# soap-disp-smd-32-channel-min.net
KiCad netlist of a schematic drawn in EasyEDA
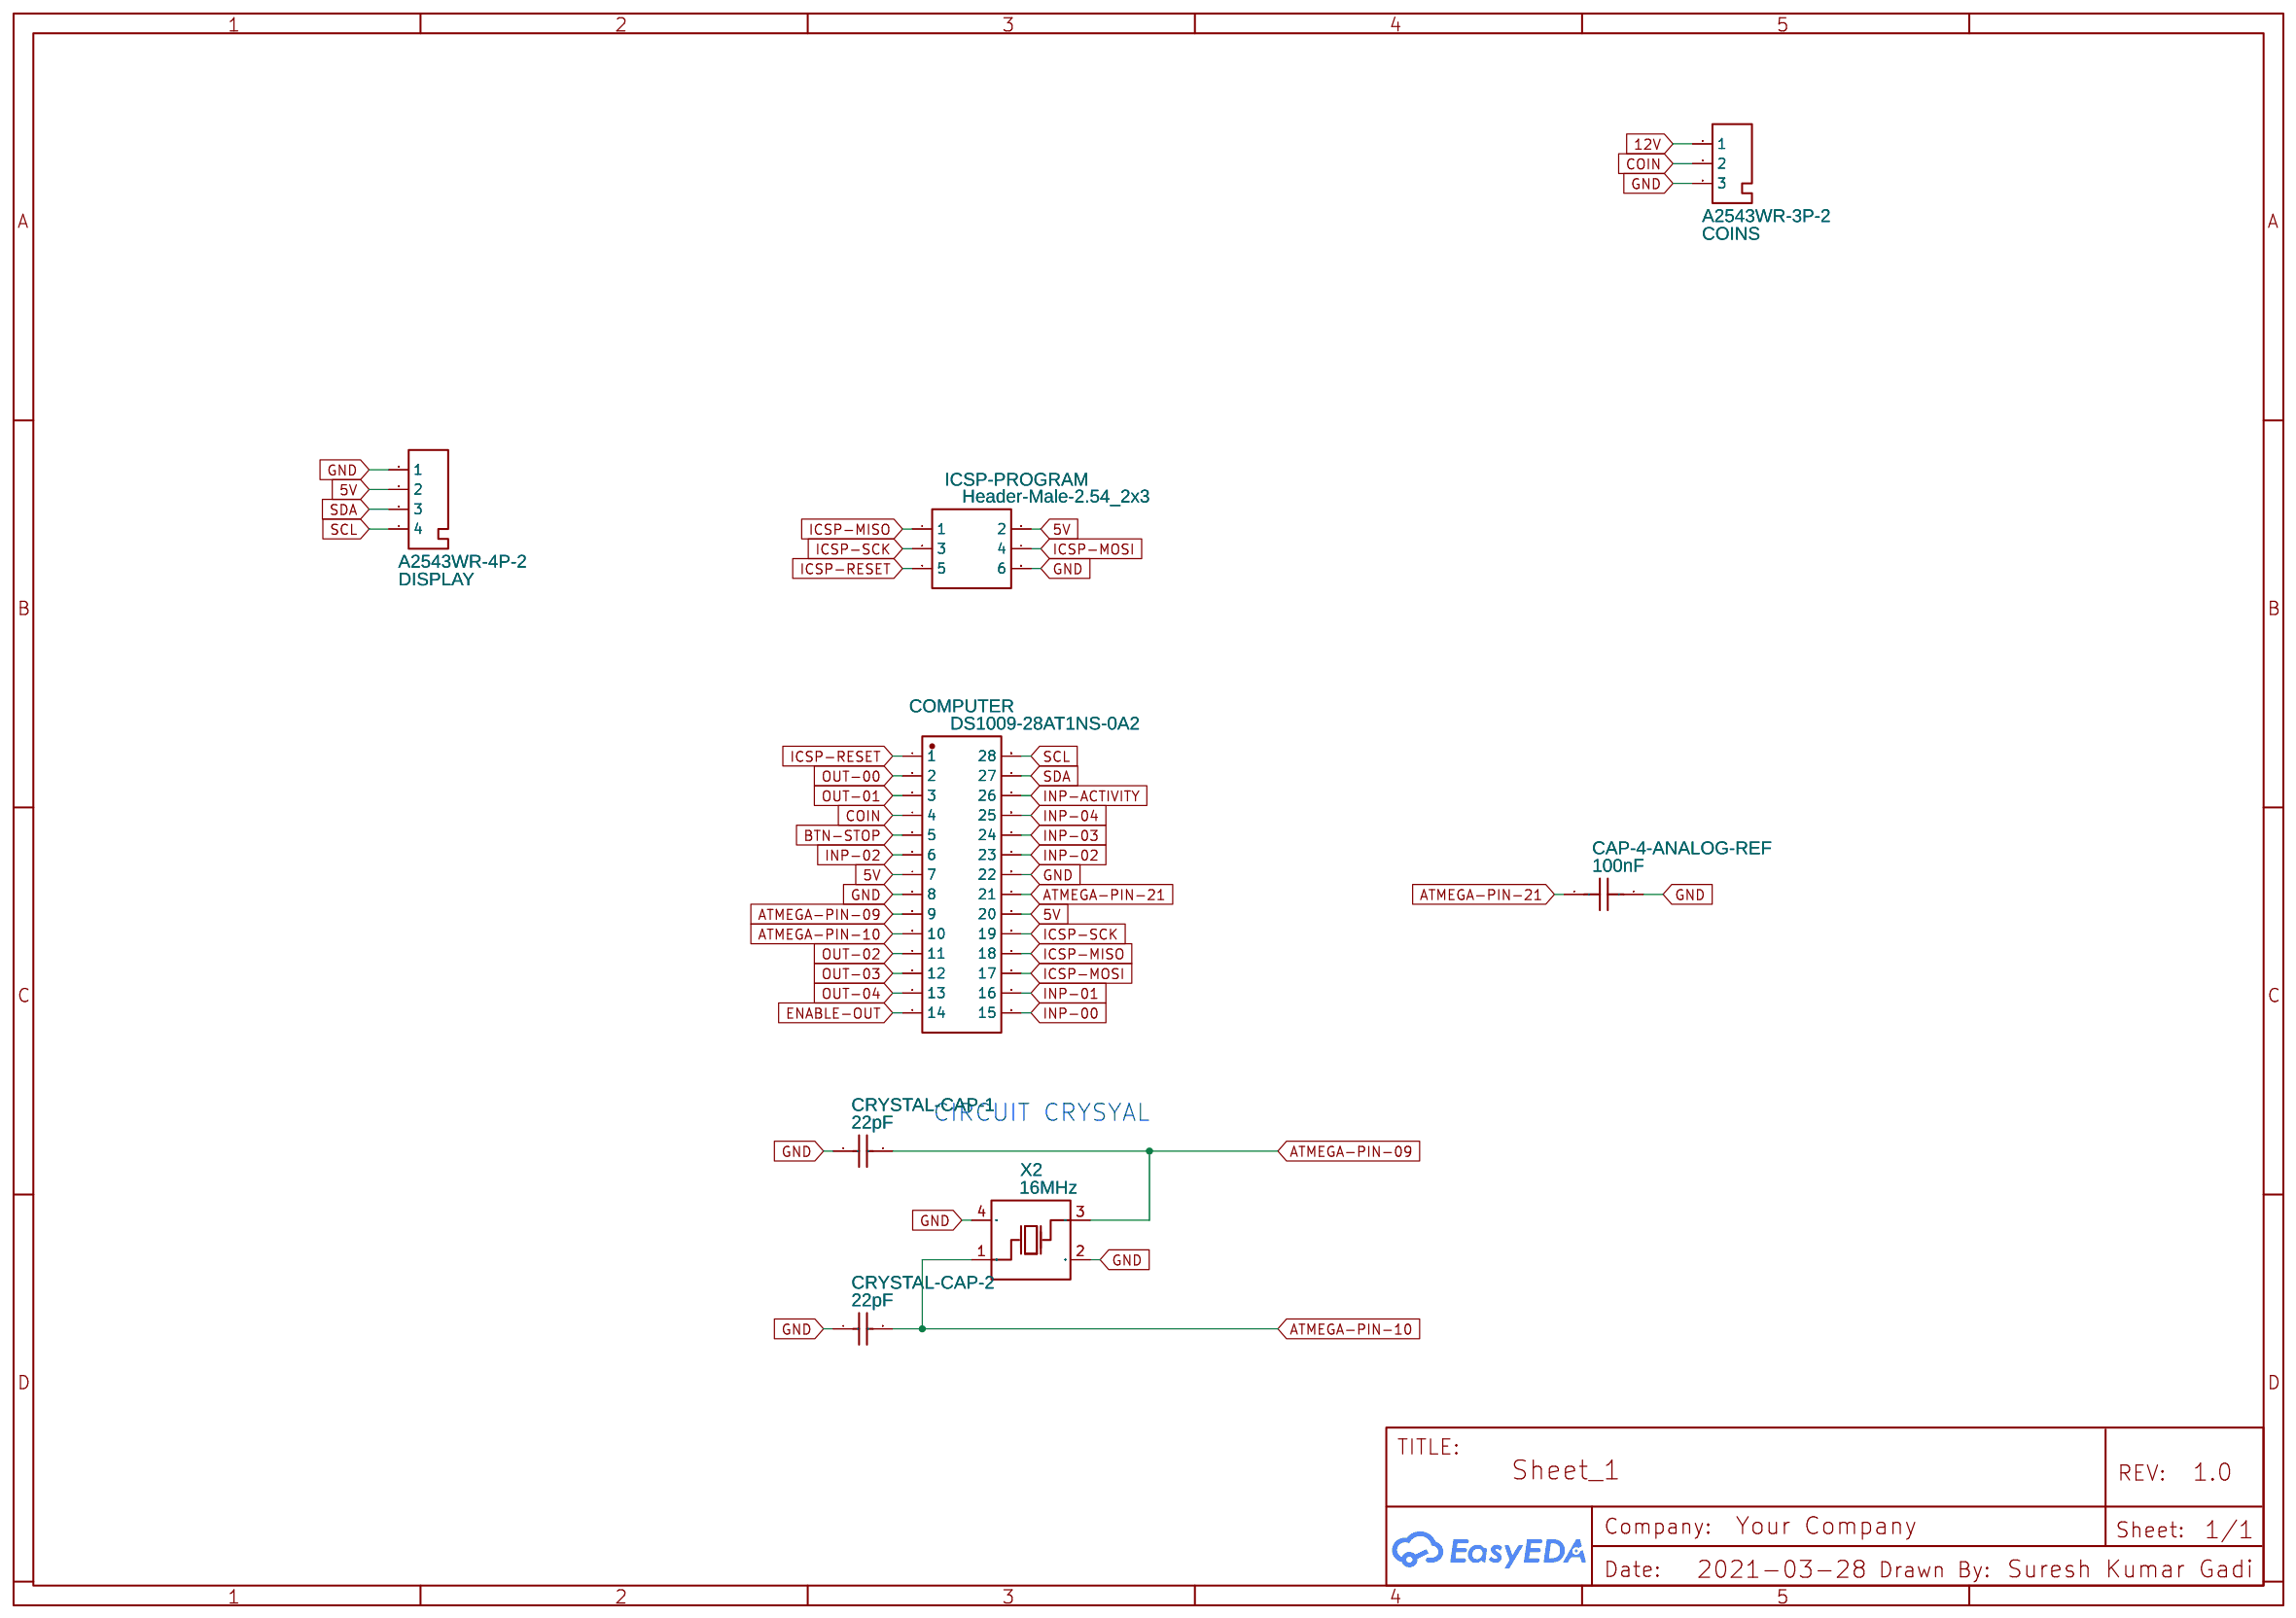
[diagram p0: Computer]
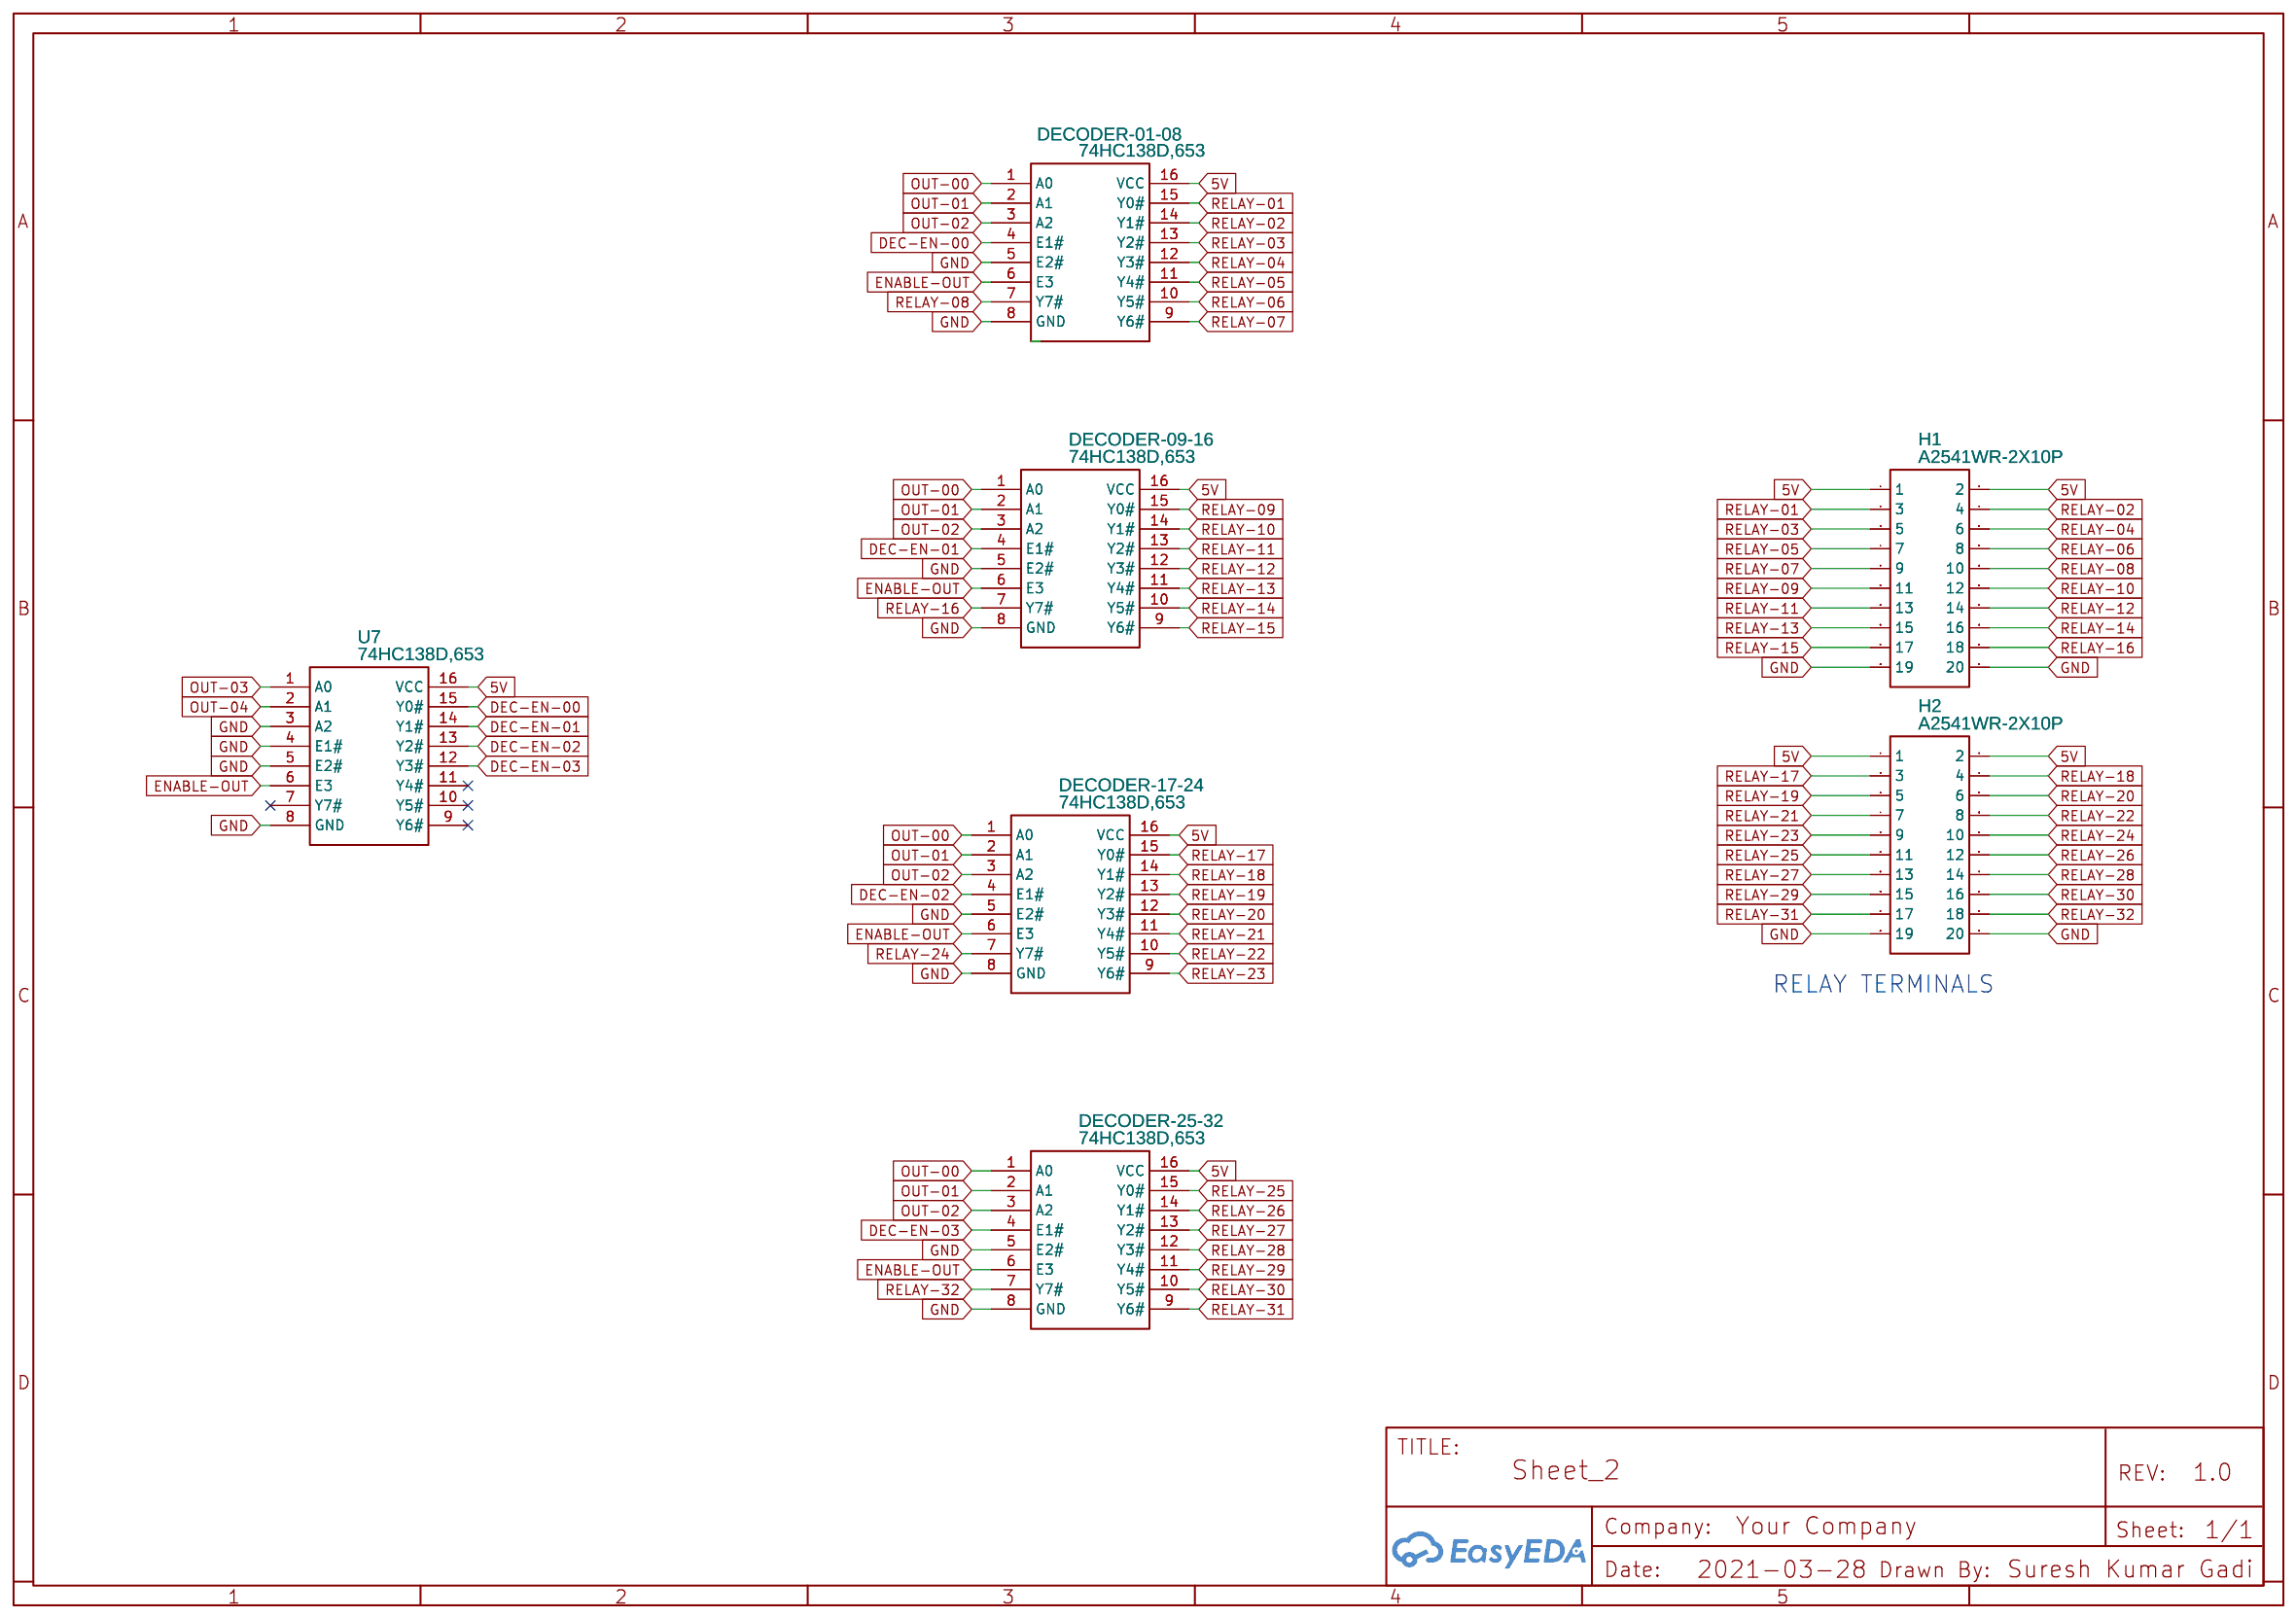
[diagram p1: Relays]
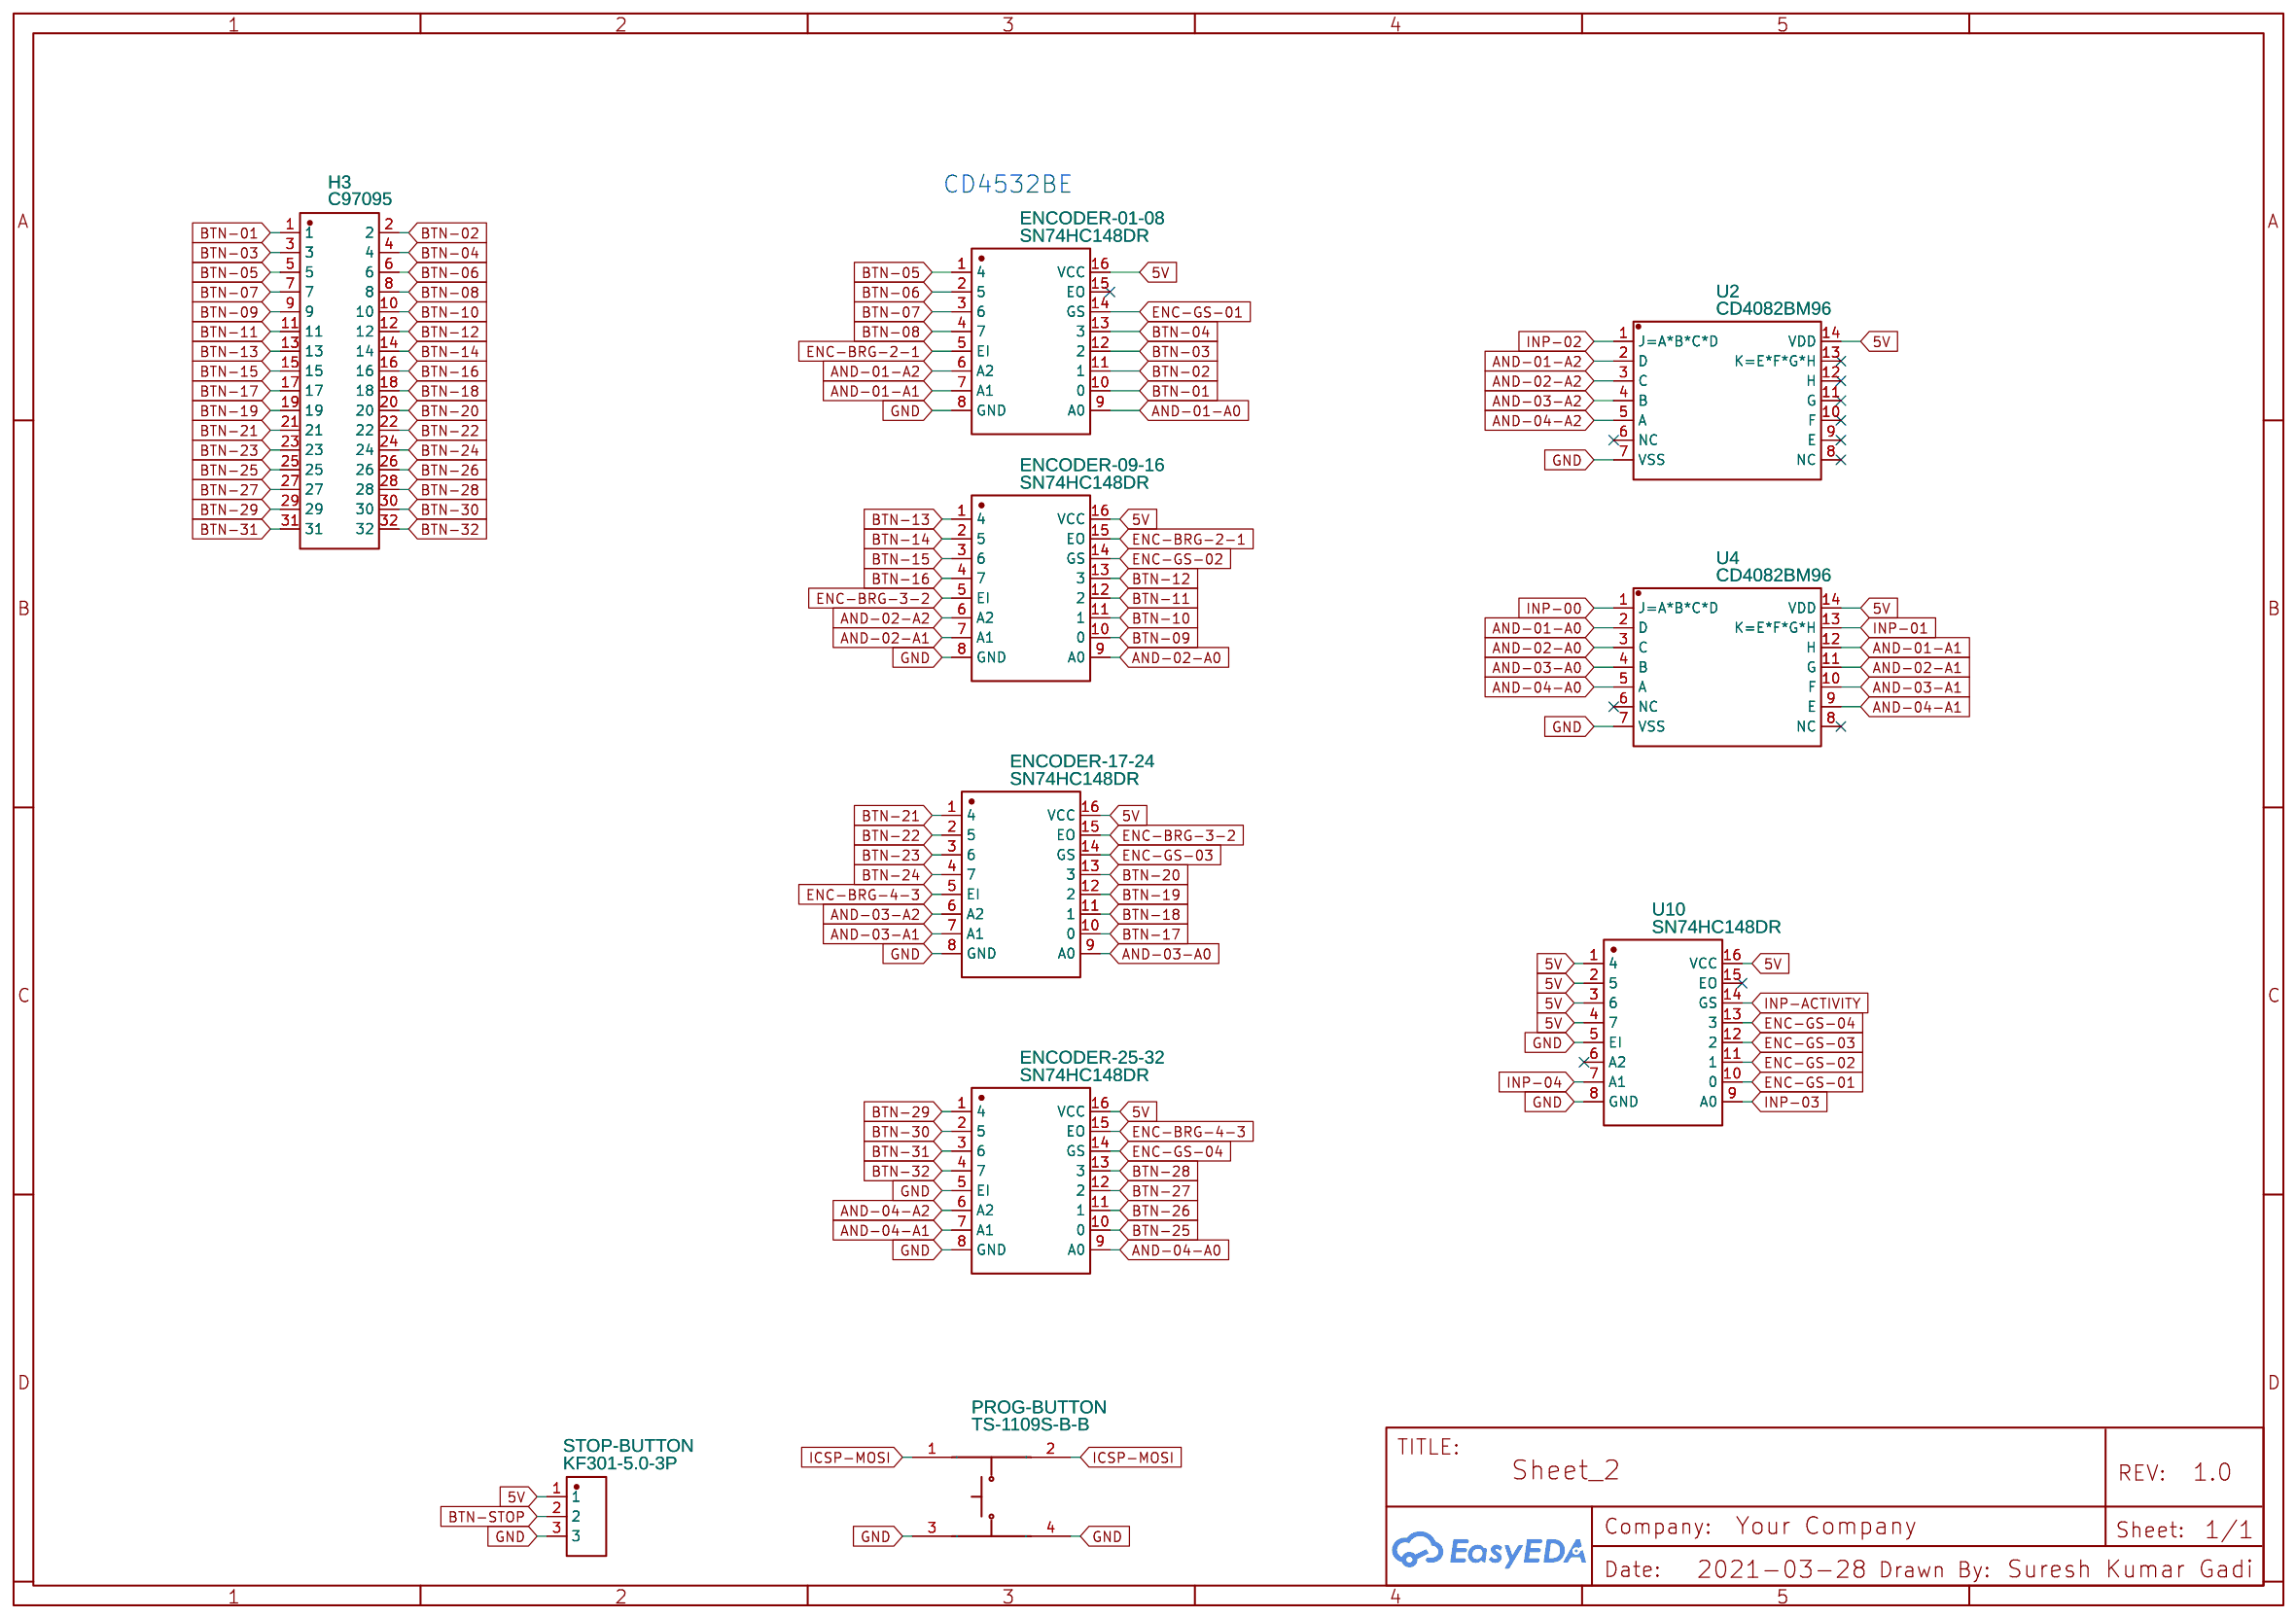
[diagram p2: Buttons]
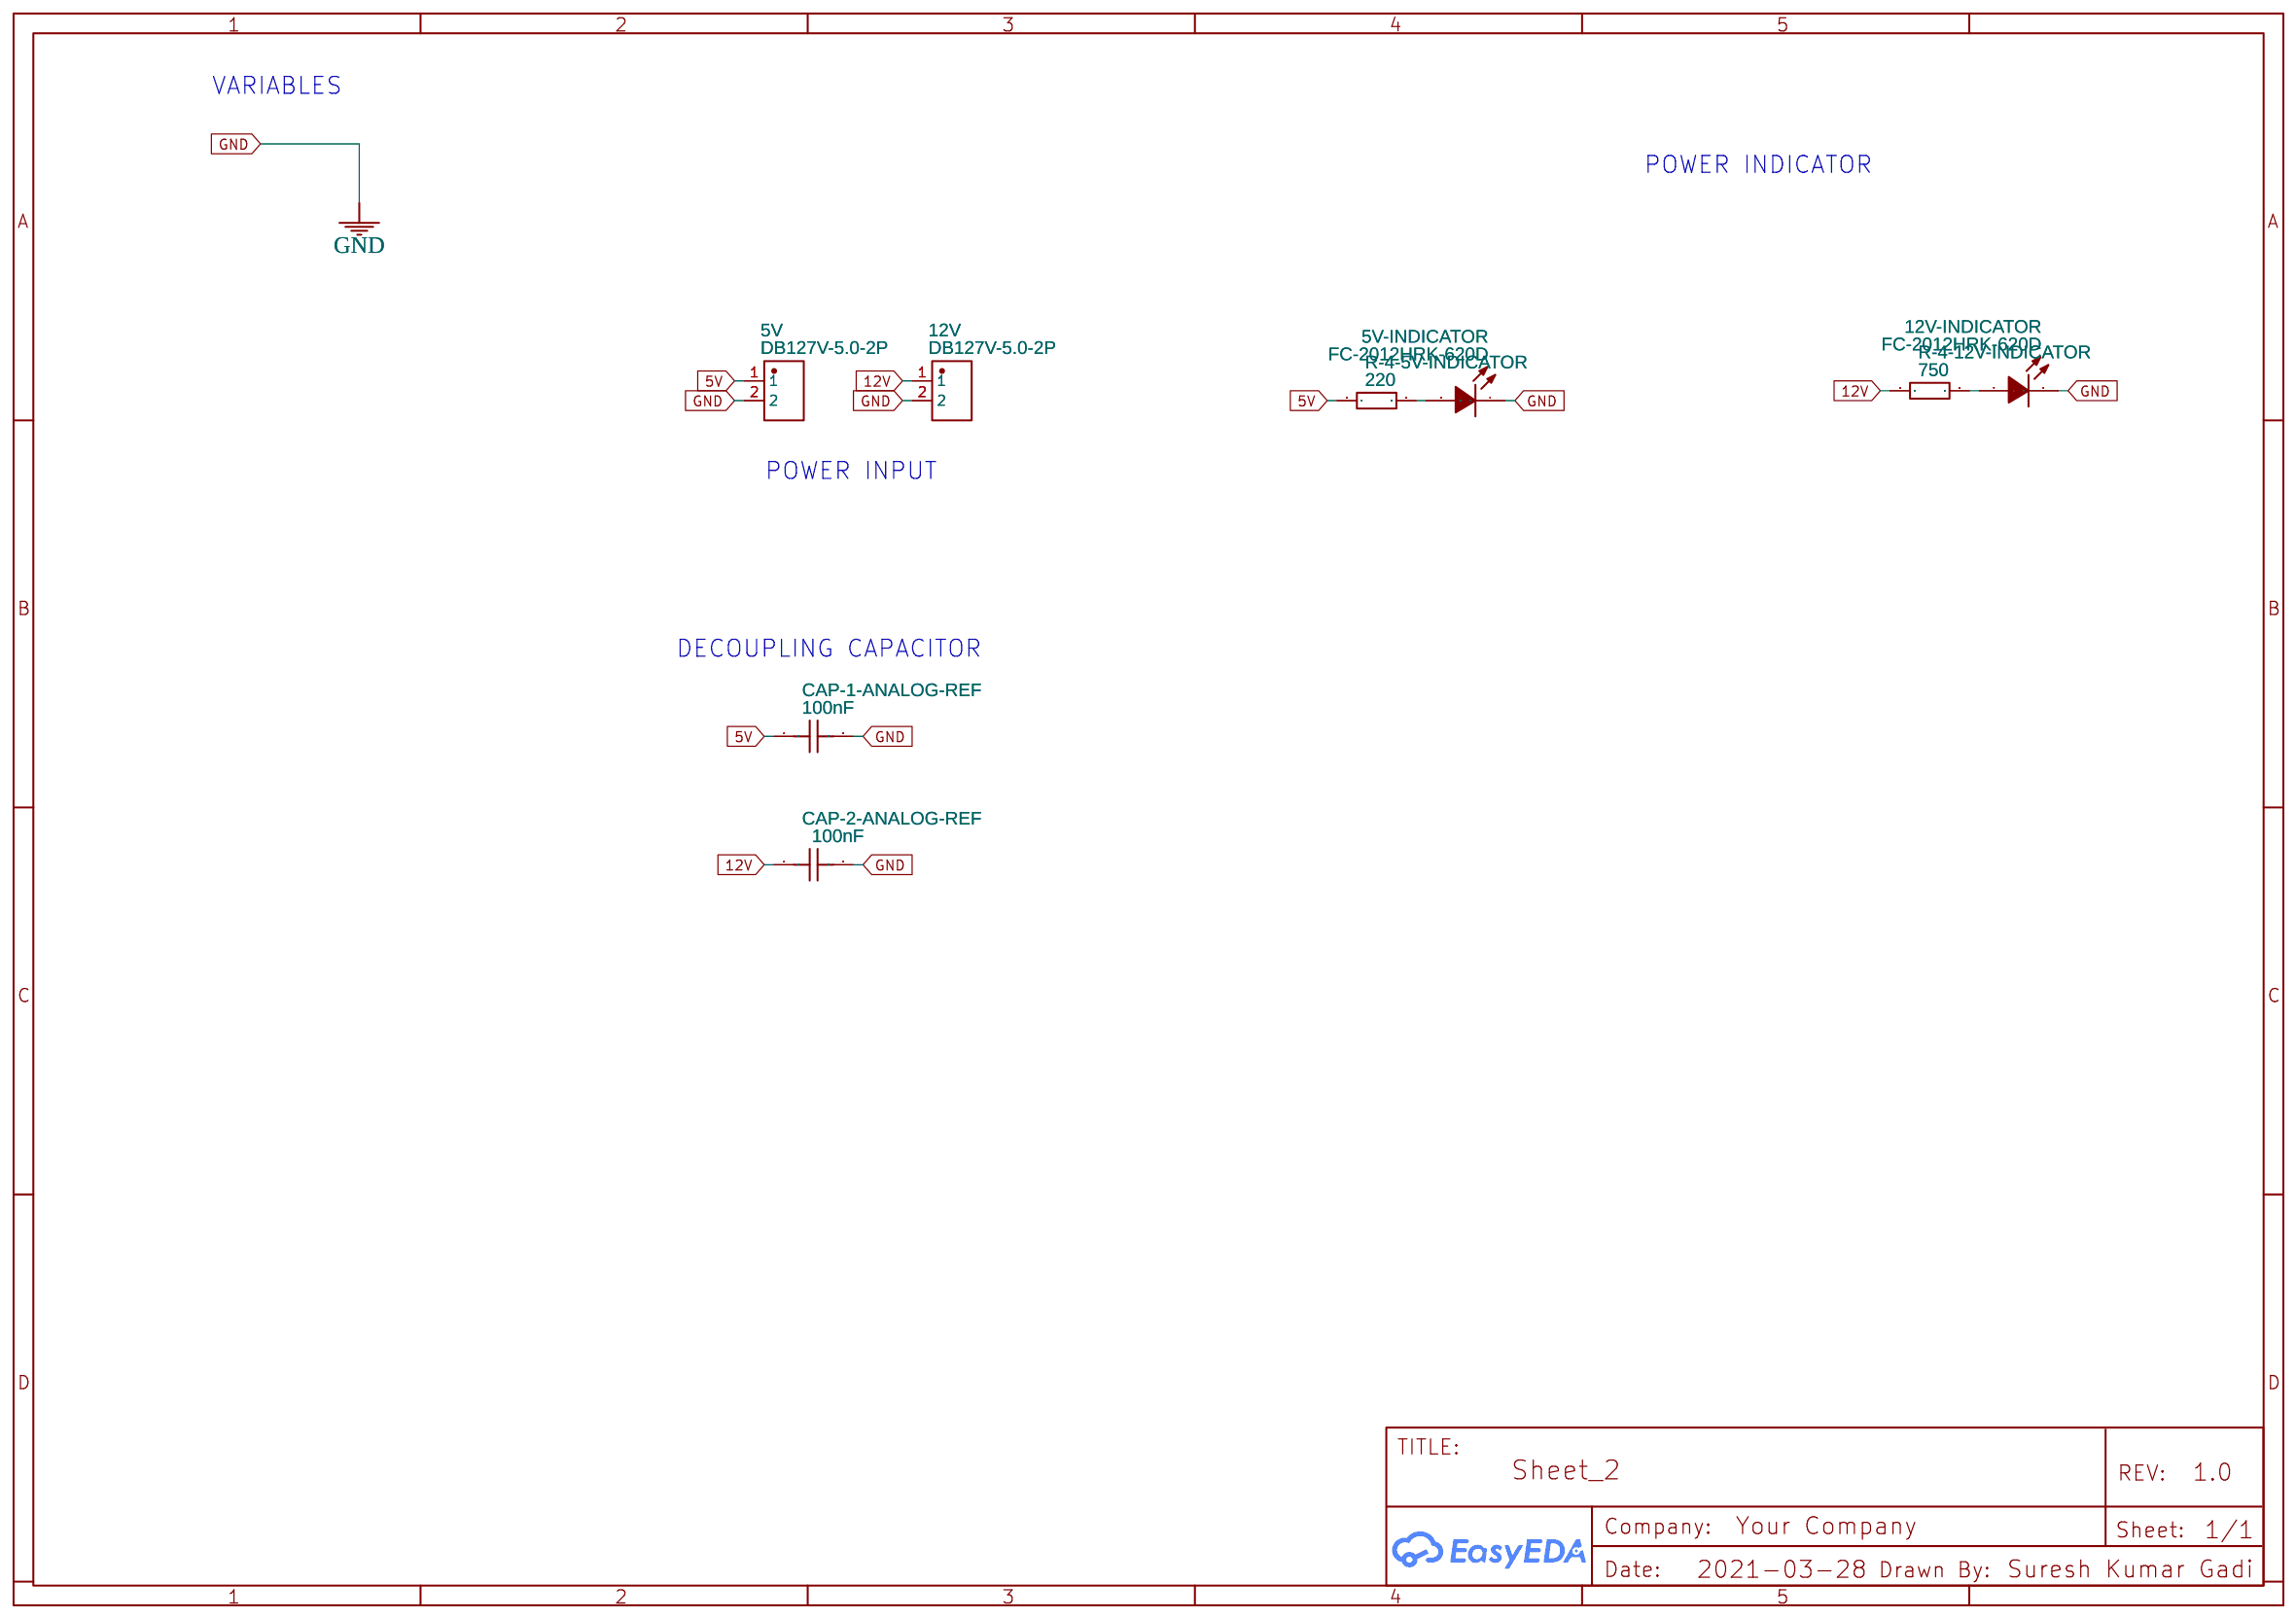
[diagram p3: Power]
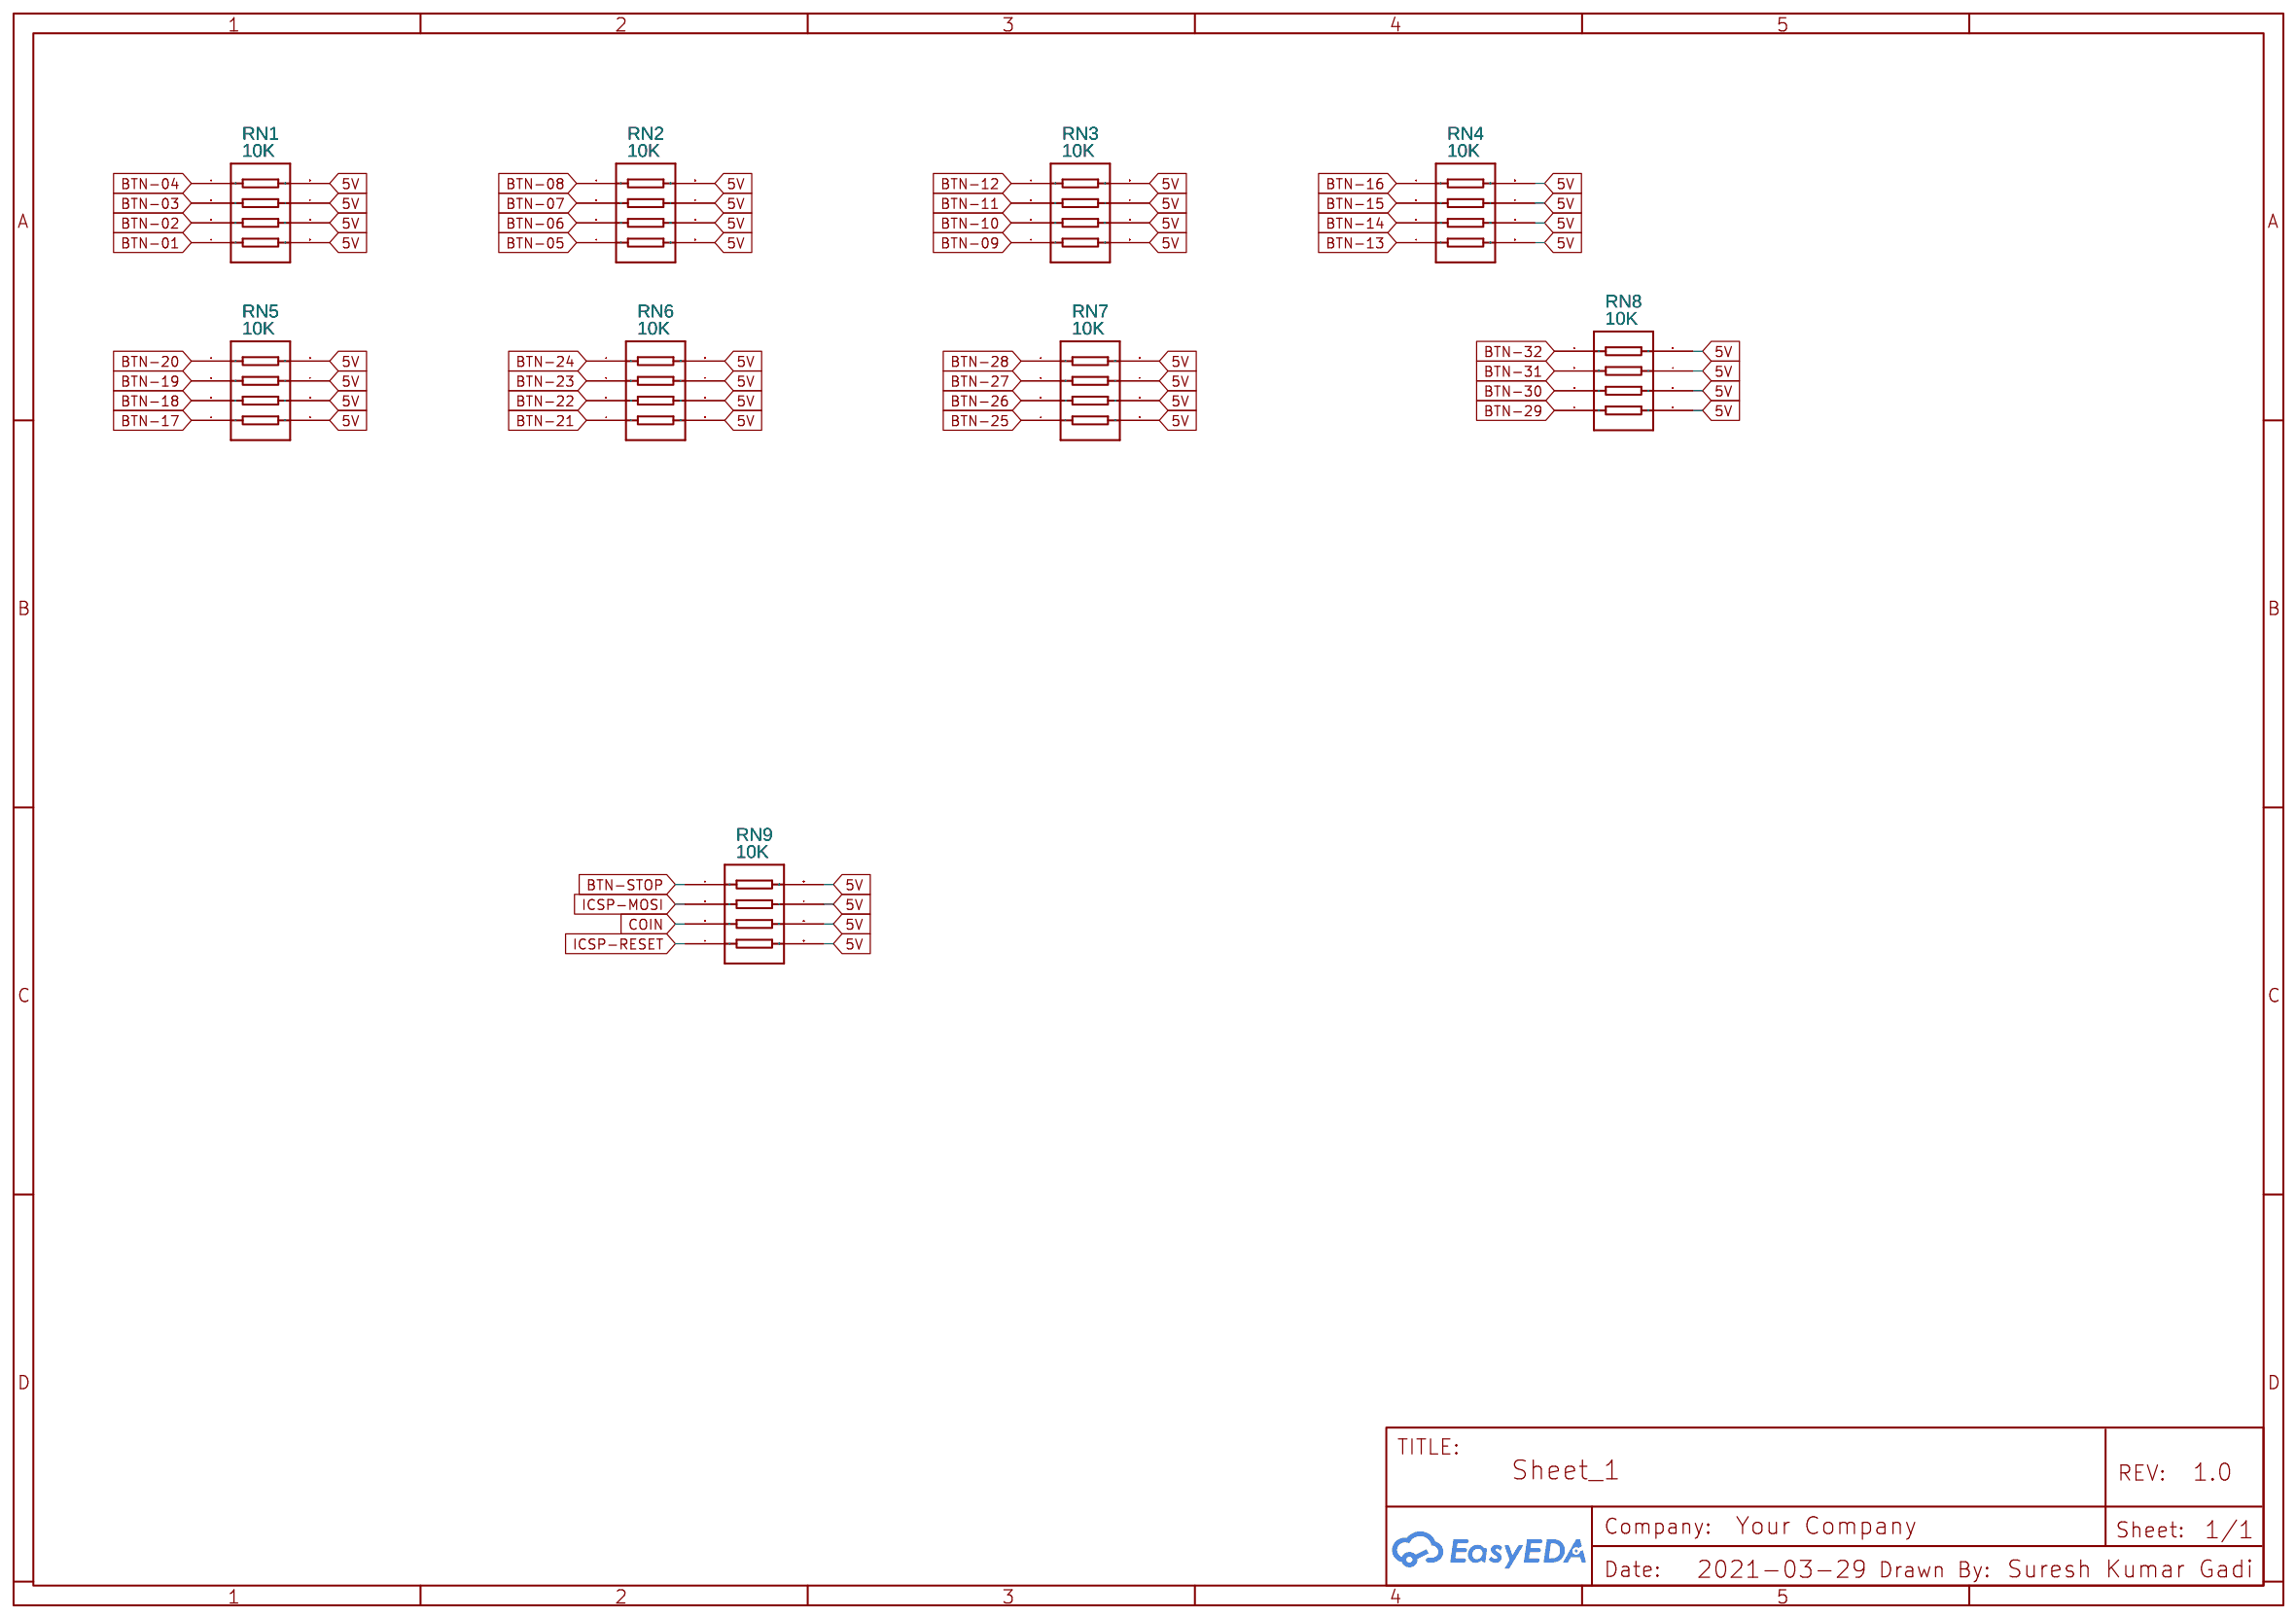
[diagram p4: Pull up-down]

(export (version "E")
  (design (tool "Eeschema 10.0.6"))
  (components
    (comp (ref "CAP-4-ANALOG-REF")
      (value "100nF")
      (fields
        (field (name "BOM_Manufacturer Part") "CC0603KRX7R9BB104")
        (field (name "BOM_Supplier Part") "C14663")
      )
      (libsource (lib "") (part "CC0603KRX7R9BB104"))
    )
    (comp (ref "COINS")
      (value "A2543WR-3P-2")
      (fields (field (name "BOM_Supplier Part") "C239370"))
      (libsource (lib "") (part "A2543WR-3P-2"))
    )
    (comp (ref "COMPUTER")
      (value "DS1009-28AT1NS-0A2")
      (fields (field (name "BOM_Supplier Part") "C72125"))
      (libsource (lib "") (part "DS1009-28AT1NS-0A2"))
    )
    (comp (ref "CRYSTAL-CAP-1")
      (value "22pF")
      (fields
        (field (name "BOM_Manufacturer Part") "CL21C220JBANNNC")
        (field (name "BOM_Supplier Part") "C1804")
      )
      (libsource (lib "") (part "CL21C220JBANNNC"))
    )
    (comp (ref "CRYSTAL-CAP-2")
      (value "22pF")
      (fields
        (field (name "BOM_Manufacturer Part") "CL21C220JBANNNC")
        (field (name "BOM_Supplier Part") "C1804")
      )
      (libsource (lib "") (part "CL21C220JBANNNC"))
    )
    (comp (ref "DISPLAY")
      (value "A2543WR-4P-2")
      (fields (field (name "BOM_Supplier Part") "C239371"))
      (libsource (lib "") (part "A2543WR-4P-2"))
    )
    (comp (ref "ICSP-PROGRAM")
      (value "Header-Male-2.54_2x3")
      (fields (field (name "BOM_Supplier Part") "C65114"))
      (libsource (lib "") (part "Header-Male-2.54_2x3"))
    )
    (comp (ref "X2")
      (value "16MHz")
      (fields
        (field (name "BOM_Manufacturer Part") "X322516MLB4SI")
        (field (name "BOM_Supplier Part") "C13738")
      )
      (libsource (lib "") (part "X322516MLB4SI"))
    )
    (comp (ref "DECODER-01-08")
      (value "74HC138D,653")
      (fields (field (name "BOM_Supplier Part") "C5602"))
      (libsource (lib "") (part "74HC138D,653"))
    )
    (comp (ref "DECODER-09-16")
      (value "74HC138D,653")
      (fields (field (name "BOM_Supplier Part") "C5602"))
      (libsource (lib "") (part "74HC138D,653_3"))
    )
    (comp (ref "DECODER-17-24")
      (value "74HC138D,653")
      (fields (field (name "BOM_Supplier Part") "C5602"))
      (libsource (lib "") (part "74HC138D,653_4"))
    )
    (comp (ref "DECODER-25-32")
      (value "74HC138D,653")
      (fields (field (name "BOM_Supplier Part") "C5602"))
      (libsource (lib "") (part "74HC138D,653_1"))
    )
    (comp (ref "H1")
      (value "A2541WR-2X10P")
      (fields
        (field (name "BOM_Manufacturer Part") "A2541WR-2x10P")
        (field (name "BOM_Supplier Part") "C239341")
      )
      (libsource (lib "") (part "A2541WR-2X10P"))
    )
    (comp (ref "H2")
      (value "A2541WR-2X10P")
      (fields
        (field (name "BOM_Manufacturer Part") "A2541WR-2x10P")
        (field (name "BOM_Supplier Part") "C239341")
      )
      (libsource (lib "") (part "A2541WR-2X10P"))
    )
    (comp (ref "U7")
      (value "74HC138D,653")
      (fields (field (name "BOM_Supplier Part") "C5602"))
      (libsource (lib "") (part "74HC138D,653_2"))
    )
    (comp (ref "ENCODER-01-08")
      (value "SN74HC148DR")
      (fields (field (name "BOM_Supplier Part") "C6819"))
      (libsource (lib "") (part "SN74HC148DR_3"))
    )
    (comp (ref "ENCODER-09-16")
      (value "SN74HC148DR")
      (fields (field (name "BOM_Supplier Part") "C6819"))
      (libsource (lib "") (part "SN74HC148DR_2"))
    )
    (comp (ref "ENCODER-17-24")
      (value "SN74HC148DR")
      (fields (field (name "BOM_Supplier Part") "C6819"))
      (libsource (lib "") (part "SN74HC148DR"))
    )
    (comp (ref "ENCODER-25-32")
      (value "SN74HC148DR")
      (fields (field (name "BOM_Supplier Part") "C6819"))
      (libsource (lib "") (part "SN74HC148DR_1"))
    )
    (comp (ref "H3") (value "C97095") (libsource (lib "") (part "C97095")))
    (comp (ref "PROG-BUTTON")
      (value "TS-1109S-B-B")
      (fields (field (name "BOM_Supplier Part") "C480315"))
      (libsource (lib "") (part "TS-1109S-B-B"))
    )
    (comp (ref "STOP-BUTTON")
      (value "KF301-5.0-3P")
      (fields (field (name "BOM_Supplier Part") "C474882"))
      (libsource (lib "") (part "KF301-5.0-3P"))
    )
    (comp (ref "U2")
      (value "CD4082BM96")
      (fields (field (name "BOM_Supplier Part") "C193801"))
      (libsource (lib "") (part "CD4082BM96"))
    )
    (comp (ref "U4")
      (value "CD4082BM96")
      (fields (field (name "BOM_Supplier Part") "C193801"))
      (libsource (lib "") (part "CD4082BM96"))
    )
    (comp (ref "U10")
      (value "SN74HC148DR")
      (fields (field (name "BOM_Supplier Part") "C6819"))
      (libsource (lib "") (part "SN74HC148DR_4"))
    )
    (comp (ref "5V")
      (value "DB127V-5.0-2P")
      (fields (field (name "BOM_Supplier Part") "C395885"))
      (libsource (lib "") (part "DB127V-5.0-2P"))
    )
    (comp (ref "5V-INDICATOR")
      (value "FC-2012HRK-620D")
      (fields (field (name "BOM_Supplier Part") "C84256"))
      (libsource (lib "") (part "FC-2012HRK-620D_1"))
    )
    (comp (ref "12V")
      (value "DB127V-5.0-2P")
      (fields (field (name "BOM_Supplier Part") "C395885"))
      (libsource (lib "") (part "DB127V-5.0-2P_1"))
    )
    (comp (ref "12V-INDICATOR")
      (value "FC-2012HRK-620D")
      (fields (field (name "BOM_Supplier Part") "C84256"))
      (libsource (lib "") (part "FC-2012HRK-620D"))
    )
    (comp (ref "CAP-1-ANALOG-REF")
      (value "100nF")
      (fields
        (field (name "BOM_Manufacturer Part") "CC0603KRX7R9BB104")
        (field (name "BOM_Supplier Part") "C14663")
      )
      (libsource (lib "") (part "CC0603KRX7R9BB104_1"))
    )
    (comp (ref "CAP-2-ANALOG-REF")
      (value "100nF")
      (fields
        (field (name "BOM_Manufacturer Part") "CC0603KRX7R9BB104")
        (field (name "BOM_Supplier Part") "C14663")
      )
      (libsource (lib "") (part "CC0603KRX7R9BB104"))
    )
    (comp (ref "R-4-5V-INDICATOR")
      (value "220")
      (fields
        (field (name "BOM_Manufacturer Part") "0805W8F2200T5E")
        (field (name "BOM_Supplier Part") "C17557")
      )
      (libsource (lib "") (part "0805W8F2200T5E"))
    )
    (comp (ref "R-4-12V-INDICATOR")
      (value "750")
      (fields
        (field (name "BOM_Manufacturer Part") "1206W4F7500T5E")
        (field (name "BOM_Supplier Part") "C17985")
      )
      (libsource (lib "") (part "1206W4F7500T5E"))
    )
    (comp (ref "RN1")
      (value "10K")
      (fields
        (field (name "BOM_Manufacturer Part") "4D03WGJ0103T5E")
        (field (name "BOM_Supplier Part") "C29718")
      )
      (libsource (lib "") (part "4D03WGJ0103T5E"))
    )
    (comp (ref "RN2")
      (value "10K")
      (fields
        (field (name "BOM_Manufacturer Part") "4D03WGJ0103T5E")
        (field (name "BOM_Supplier Part") "C29718")
      )
      (libsource (lib "") (part "4D03WGJ0103T5E"))
    )
    (comp (ref "RN3")
      (value "10K")
      (fields
        (field (name "BOM_Manufacturer Part") "4D03WGJ0103T5E")
        (field (name "BOM_Supplier Part") "C29718")
      )
      (libsource (lib "") (part "4D03WGJ0103T5E"))
    )
    (comp (ref "RN4")
      (value "10K")
      (fields
        (field (name "BOM_Manufacturer Part") "4D03WGJ0103T5E")
        (field (name "BOM_Supplier Part") "C29718")
      )
      (libsource (lib "") (part "4D03WGJ0103T5E"))
    )
    (comp (ref "RN5")
      (value "10K")
      (fields
        (field (name "BOM_Manufacturer Part") "4D03WGJ0103T5E")
        (field (name "BOM_Supplier Part") "C29718")
      )
      (libsource (lib "") (part "4D03WGJ0103T5E"))
    )
    (comp (ref "RN6")
      (value "10K")
      (fields
        (field (name "BOM_Manufacturer Part") "4D03WGJ0103T5E")
        (field (name "BOM_Supplier Part") "C29718")
      )
      (libsource (lib "") (part "4D03WGJ0103T5E"))
    )
    (comp (ref "RN7")
      (value "10K")
      (fields
        (field (name "BOM_Manufacturer Part") "4D03WGJ0103T5E")
        (field (name "BOM_Supplier Part") "C29718")
      )
      (libsource (lib "") (part "4D03WGJ0103T5E"))
    )
    (comp (ref "RN8")
      (value "10K")
      (fields
        (field (name "BOM_Manufacturer Part") "4D03WGJ0103T5E")
        (field (name "BOM_Supplier Part") "C29718")
      )
      (libsource (lib "") (part "4D03WGJ0103T5E"))
    )
    (comp (ref "RN9")
      (value "10K")
      (fields
        (field (name "BOM_Manufacturer Part") "4D03WGJ0103T5E")
        (field (name "BOM_Supplier Part") "C29718")
      )
      (libsource (lib "") (part "4D03WGJ0103T5E"))
    )
  )
  (nets
    (net (code "1") (name "5V") (class "Default")
      (node (ref "5V") (pin "1") (pinfunction "1_1") (pintype "unspecified"))
      (node (ref "CAP-1-ANALOG-REF") (pin "1") (pinfunction "1_1") (pintype "unspecified"))
      (node (ref "COMPUTER") (pin "20") (pinfunction "20_20") (pintype "unspecified"))
      (node (ref "COMPUTER") (pin "7") (pinfunction "7_7") (pintype "unspecified"))
      (node (ref "DECODER-01-08") (pin "16") (pinfunction "VCC_16") (pintype "unspecified"))
      (node (ref "DECODER-09-16") (pin "16") (pinfunction "VCC_16") (pintype "unspecified"))
      (node (ref "DECODER-17-24") (pin "16") (pinfunction "VCC_16") (pintype "unspecified"))
      (node (ref "DECODER-25-32") (pin "16") (pinfunction "VCC_16") (pintype "unspecified"))
      (node (ref "DISPLAY") (pin "2") (pinfunction "2_2") (pintype "unspecified"))
      (node (ref "ENCODER-01-08") (pin "16") (pinfunction "VCC_16") (pintype "unspecified"))
      (node (ref "ENCODER-09-16") (pin "16") (pinfunction "VCC_16") (pintype "unspecified"))
      (node (ref "ENCODER-17-24") (pin "16") (pinfunction "VCC_16") (pintype "unspecified"))
      (node (ref "ENCODER-25-32") (pin "16") (pinfunction "VCC_16") (pintype "unspecified"))
      (node (ref "H1") (pin "1") (pinfunction "1_1") (pintype "unspecified"))
      (node (ref "H1") (pin "2") (pinfunction "2_2") (pintype "unspecified"))
      (node (ref "H2") (pin "1") (pinfunction "1_1") (pintype "unspecified"))
      (node (ref "H2") (pin "2") (pinfunction "2_2") (pintype "unspecified"))
      (node (ref "ICSP-PROGRAM") (pin "2") (pinfunction "2_2") (pintype "input"))
      (node (ref "R-4-5V-INDICATOR") (pin "1") (pinfunction "1_1") (pintype "input"))
      (node (ref "RN1") (pin "5") (pinfunction "5_5") (pintype "input"))
      (node (ref "RN1") (pin "6") (pinfunction "6_6") (pintype "input"))
      (node (ref "RN1") (pin "7") (pinfunction "7_7") (pintype "input"))
      (node (ref "RN1") (pin "8") (pinfunction "8_8") (pintype "input"))
      (node (ref "RN2") (pin "5") (pinfunction "5_5") (pintype "input"))
      (node (ref "RN2") (pin "6") (pinfunction "6_6") (pintype "input"))
      (node (ref "RN2") (pin "7") (pinfunction "7_7") (pintype "input"))
      (node (ref "RN2") (pin "8") (pinfunction "8_8") (pintype "input"))
      (node (ref "RN3") (pin "5") (pinfunction "5_5") (pintype "input"))
      (node (ref "RN3") (pin "6") (pinfunction "6_6") (pintype "input"))
      (node (ref "RN3") (pin "7") (pinfunction "7_7") (pintype "input"))
      (node (ref "RN3") (pin "8") (pinfunction "8_8") (pintype "input"))
      (node (ref "RN4") (pin "5") (pinfunction "5_5") (pintype "input"))
      (node (ref "RN4") (pin "6") (pinfunction "6_6") (pintype "input"))
      (node (ref "RN4") (pin "7") (pinfunction "7_7") (pintype "input"))
      (node (ref "RN4") (pin "8") (pinfunction "8_8") (pintype "input"))
      (node (ref "RN5") (pin "5") (pinfunction "5_5") (pintype "input"))
      (node (ref "RN5") (pin "6") (pinfunction "6_6") (pintype "input"))
      (node (ref "RN5") (pin "7") (pinfunction "7_7") (pintype "input"))
      (node (ref "RN5") (pin "8") (pinfunction "8_8") (pintype "input"))
      (node (ref "RN6") (pin "5") (pinfunction "5_5") (pintype "input"))
      (node (ref "RN6") (pin "6") (pinfunction "6_6") (pintype "input"))
      (node (ref "RN6") (pin "7") (pinfunction "7_7") (pintype "input"))
      (node (ref "RN6") (pin "8") (pinfunction "8_8") (pintype "input"))
      (node (ref "RN7") (pin "5") (pinfunction "5_5") (pintype "input"))
      (node (ref "RN7") (pin "6") (pinfunction "6_6") (pintype "input"))
      (node (ref "RN7") (pin "7") (pinfunction "7_7") (pintype "input"))
      (node (ref "RN7") (pin "8") (pinfunction "8_8") (pintype "input"))
      (node (ref "RN8") (pin "5") (pinfunction "5_5") (pintype "input"))
      (node (ref "RN8") (pin "6") (pinfunction "6_6") (pintype "input"))
      (node (ref "RN8") (pin "7") (pinfunction "7_7") (pintype "input"))
      (node (ref "RN8") (pin "8") (pinfunction "8_8") (pintype "input"))
      (node (ref "RN9") (pin "5") (pinfunction "5_5") (pintype "input"))
      (node (ref "RN9") (pin "6") (pinfunction "6_6") (pintype "input"))
      (node (ref "RN9") (pin "7") (pinfunction "7_7") (pintype "input"))
      (node (ref "RN9") (pin "8") (pinfunction "8_8") (pintype "input"))
      (node (ref "STOP-BUTTON") (pin "1") (pinfunction "1_1") (pintype "unspecified"))
      (node (ref "U10") (pin "1") (pinfunction "4_1") (pintype "unspecified"))
      (node (ref "U10") (pin "16") (pinfunction "VCC_16") (pintype "unspecified"))
      (node (ref "U10") (pin "2") (pinfunction "5_2") (pintype "unspecified"))
      (node (ref "U10") (pin "3") (pinfunction "6_3") (pintype "unspecified"))
      (node (ref "U10") (pin "4") (pinfunction "7_4") (pintype "unspecified"))
      (node (ref "U2") (pin "14") (pinfunction "VDD_14") (pintype "unspecified"))
      (node (ref "U4") (pin "14") (pinfunction "VDD_14") (pintype "unspecified"))
      (node (ref "U7") (pin "16") (pinfunction "VCC_16") (pintype "unspecified"))
    )
    (net (code "2") (name "12V") (class "Default")
      (node (ref "12V") (pin "1") (pinfunction "1_1") (pintype "unspecified"))
      (node (ref "CAP-2-ANALOG-REF") (pin "1") (pinfunction "1_1") (pintype "unspecified"))
      (node (ref "COINS") (pin "1") (pinfunction "1_1") (pintype "unspecified"))
      (node (ref "R-4-12V-INDICATOR") (pin "1") (pinfunction "1_1") (pintype "input"))
    )
    (net (code "3") (name "AND-01-A0") (class "Default")
      (node (ref "ENCODER-01-08") (pin "9") (pinfunction "A0_9") (pintype "unspecified"))
      (node (ref "U4") (pin "2") (pinfunction "D_2") (pintype "unspecified"))
    )
    (net (code "4") (name "AND-01-A1") (class "Default")
      (node (ref "ENCODER-01-08") (pin "7") (pinfunction "A1_7") (pintype "unspecified"))
      (node (ref "U4") (pin "12") (pinfunction "H_12") (pintype "unspecified"))
    )
    (net (code "5") (name "AND-01-A2") (class "Default")
      (node (ref "ENCODER-01-08") (pin "6") (pinfunction "A2_6") (pintype "unspecified"))
      (node (ref "U2") (pin "2") (pinfunction "D_2") (pintype "unspecified"))
    )
    (net (code "6") (name "AND-02-A0") (class "Default")
      (node (ref "ENCODER-09-16") (pin "9") (pinfunction "A0_9") (pintype "unspecified"))
      (node (ref "U4") (pin "3") (pinfunction "C_3") (pintype "unspecified"))
    )
    (net (code "7") (name "AND-02-A1") (class "Default")
      (node (ref "ENCODER-09-16") (pin "7") (pinfunction "A1_7") (pintype "unspecified"))
      (node (ref "U4") (pin "11") (pinfunction "G_11") (pintype "unspecified"))
    )
    (net (code "8") (name "AND-02-A2") (class "Default")
      (node (ref "ENCODER-09-16") (pin "6") (pinfunction "A2_6") (pintype "unspecified"))
      (node (ref "U2") (pin "3") (pinfunction "C_3") (pintype "unspecified"))
    )
    (net (code "9") (name "AND-03-A0") (class "Default")
      (node (ref "ENCODER-17-24") (pin "9") (pinfunction "A0_9") (pintype "unspecified"))
      (node (ref "U4") (pin "4") (pinfunction "B_4") (pintype "unspecified"))
    )
    (net (code "10") (name "AND-03-A1") (class "Default")
      (node (ref "ENCODER-17-24") (pin "7") (pinfunction "A1_7") (pintype "unspecified"))
      (node (ref "U4") (pin "10") (pinfunction "F_10") (pintype "unspecified"))
    )
    (net (code "11") (name "AND-03-A2") (class "Default")
      (node (ref "ENCODER-17-24") (pin "6") (pinfunction "A2_6") (pintype "unspecified"))
      (node (ref "U2") (pin "4") (pinfunction "B_4") (pintype "unspecified"))
    )
    (net (code "12") (name "AND-04-A0") (class "Default")
      (node (ref "ENCODER-25-32") (pin "9") (pinfunction "A0_9") (pintype "unspecified"))
      (node (ref "U4") (pin "5") (pinfunction "A_5") (pintype "unspecified"))
    )
    (net (code "13") (name "AND-04-A1") (class "Default")
      (node (ref "ENCODER-25-32") (pin "7") (pinfunction "A1_7") (pintype "unspecified"))
      (node (ref "U4") (pin "9") (pinfunction "E_9") (pintype "unspecified"))
    )
    (net (code "14") (name "AND-04-A2") (class "Default")
      (node (ref "ENCODER-25-32") (pin "6") (pinfunction "A2_6") (pintype "unspecified"))
      (node (ref "U2") (pin "5") (pinfunction "A_5") (pintype "unspecified"))
    )
    (net (code "15") (name "ATMEGA-PIN-09") (class "Default")
      (node (ref "COMPUTER") (pin "9") (pinfunction "9_9") (pintype "unspecified"))
      (node (ref "CRYSTAL-CAP-1") (pin "2") (pinfunction "2_2") (pintype "input"))
      (node (ref "X2") (pin "3") (pinfunction "OSC2_3") (pintype "unspecified"))
    )
    (net (code "16") (name "ATMEGA-PIN-10") (class "Default")
      (node (ref "COMPUTER") (pin "10") (pinfunction "10_10") (pintype "unspecified"))
      (node (ref "CRYSTAL-CAP-2") (pin "2") (pinfunction "2_2") (pintype "input"))
      (node (ref "X2") (pin "1") (pinfunction "OSC1_1") (pintype "unspecified"))
    )
    (net (code "17") (name "ATMEGA-PIN-21") (class "Default")
      (node (ref "CAP-4-ANALOG-REF") (pin "1") (pinfunction "1_1") (pintype "unspecified"))
      (node (ref "COMPUTER") (pin "21") (pinfunction "21_21") (pintype "unspecified"))
    )
    (net (code "18") (name "BTN-01") (class "Default")
      (node (ref "ENCODER-01-08") (pin "10") (pinfunction "0_10") (pintype "unspecified"))
      (node (ref "H3") (pin "1") (pinfunction "1_1") (pintype "unspecified"))
      (node (ref "RN1") (pin "4") (pinfunction "4_4") (pintype "input"))
    )
    (net (code "19") (name "BTN-02") (class "Default")
      (node (ref "ENCODER-01-08") (pin "11") (pinfunction "1_11") (pintype "unspecified"))
      (node (ref "H3") (pin "2") (pinfunction "2_2") (pintype "unspecified"))
      (node (ref "RN1") (pin "3") (pinfunction "3_3") (pintype "input"))
    )
    (net (code "20") (name "BTN-03") (class "Default")
      (node (ref "ENCODER-01-08") (pin "12") (pinfunction "2_12") (pintype "unspecified"))
      (node (ref "H3") (pin "3") (pinfunction "3_3") (pintype "unspecified"))
      (node (ref "RN1") (pin "2") (pinfunction "2_2") (pintype "input"))
    )
    (net (code "21") (name "BTN-04") (class "Default")
      (node (ref "ENCODER-01-08") (pin "13") (pinfunction "3_13") (pintype "unspecified"))
      (node (ref "H3") (pin "4") (pinfunction "4_4") (pintype "unspecified"))
      (node (ref "RN1") (pin "1") (pinfunction "1_1") (pintype "input"))
    )
    (net (code "22") (name "BTN-05") (class "Default")
      (node (ref "ENCODER-01-08") (pin "1") (pinfunction "4_1") (pintype "unspecified"))
      (node (ref "H3") (pin "5") (pinfunction "5_5") (pintype "unspecified"))
      (node (ref "RN2") (pin "4") (pinfunction "4_4") (pintype "input"))
    )
    (net (code "23") (name "BTN-06") (class "Default")
      (node (ref "ENCODER-01-08") (pin "2") (pinfunction "5_2") (pintype "unspecified"))
      (node (ref "H3") (pin "6") (pinfunction "6_6") (pintype "unspecified"))
      (node (ref "RN2") (pin "3") (pinfunction "3_3") (pintype "input"))
    )
    (net (code "24") (name "BTN-07") (class "Default")
      (node (ref "ENCODER-01-08") (pin "3") (pinfunction "6_3") (pintype "unspecified"))
      (node (ref "H3") (pin "7") (pinfunction "7_7") (pintype "unspecified"))
      (node (ref "RN2") (pin "2") (pinfunction "2_2") (pintype "input"))
    )
    (net (code "25") (name "BTN-08") (class "Default")
      (node (ref "ENCODER-01-08") (pin "4") (pinfunction "7_4") (pintype "unspecified"))
      (node (ref "H3") (pin "8") (pinfunction "8_8") (pintype "unspecified"))
      (node (ref "RN2") (pin "1") (pinfunction "1_1") (pintype "input"))
    )
    (net (code "26") (name "BTN-09") (class "Default")
      (node (ref "ENCODER-09-16") (pin "10") (pinfunction "0_10") (pintype "unspecified"))
      (node (ref "H3") (pin "9") (pinfunction "9_9") (pintype "unspecified"))
      (node (ref "RN3") (pin "4") (pinfunction "4_4") (pintype "input"))
    )
    (net (code "27") (name "BTN-10") (class "Default")
      (node (ref "ENCODER-09-16") (pin "11") (pinfunction "1_11") (pintype "unspecified"))
      (node (ref "H3") (pin "10") (pinfunction "10_10") (pintype "unspecified"))
      (node (ref "RN3") (pin "3") (pinfunction "3_3") (pintype "input"))
    )
    (net (code "28") (name "BTN-11") (class "Default")
      (node (ref "ENCODER-09-16") (pin "12") (pinfunction "2_12") (pintype "unspecified"))
      (node (ref "H3") (pin "11") (pinfunction "11_11") (pintype "unspecified"))
      (node (ref "RN3") (pin "2") (pinfunction "2_2") (pintype "input"))
    )
    (net (code "29") (name "BTN-12") (class "Default")
      (node (ref "ENCODER-09-16") (pin "13") (pinfunction "3_13") (pintype "unspecified"))
      (node (ref "H3") (pin "12") (pinfunction "12_12") (pintype "unspecified"))
      (node (ref "RN3") (pin "1") (pinfunction "1_1") (pintype "input"))
    )
    (net (code "30") (name "BTN-13") (class "Default")
      (node (ref "ENCODER-09-16") (pin "1") (pinfunction "4_1") (pintype "unspecified"))
      (node (ref "H3") (pin "13") (pinfunction "13_13") (pintype "unspecified"))
      (node (ref "RN4") (pin "4") (pinfunction "4_4") (pintype "input"))
    )
    (net (code "31") (name "BTN-14") (class "Default")
      (node (ref "ENCODER-09-16") (pin "2") (pinfunction "5_2") (pintype "unspecified"))
      (node (ref "H3") (pin "14") (pinfunction "14_14") (pintype "unspecified"))
      (node (ref "RN4") (pin "3") (pinfunction "3_3") (pintype "input"))
    )
    (net (code "32") (name "BTN-15") (class "Default")
      (node (ref "ENCODER-09-16") (pin "3") (pinfunction "6_3") (pintype "unspecified"))
      (node (ref "H3") (pin "15") (pinfunction "15_15") (pintype "unspecified"))
      (node (ref "RN4") (pin "2") (pinfunction "2_2") (pintype "input"))
    )
    (net (code "33") (name "BTN-16") (class "Default")
      (node (ref "ENCODER-09-16") (pin "4") (pinfunction "7_4") (pintype "unspecified"))
      (node (ref "H3") (pin "16") (pinfunction "16_16") (pintype "unspecified"))
      (node (ref "RN4") (pin "1") (pinfunction "1_1") (pintype "input"))
    )
    (net (code "34") (name "BTN-17") (class "Default")
      (node (ref "ENCODER-17-24") (pin "10") (pinfunction "0_10") (pintype "unspecified"))
      (node (ref "H3") (pin "17") (pinfunction "17_17") (pintype "unspecified"))
      (node (ref "RN5") (pin "4") (pinfunction "4_4") (pintype "input"))
    )
    (net (code "35") (name "BTN-18") (class "Default")
      (node (ref "ENCODER-17-24") (pin "11") (pinfunction "1_11") (pintype "unspecified"))
      (node (ref "H3") (pin "18") (pinfunction "18_18") (pintype "unspecified"))
      (node (ref "RN5") (pin "3") (pinfunction "3_3") (pintype "input"))
    )
    (net (code "36") (name "BTN-19") (class "Default")
      (node (ref "ENCODER-17-24") (pin "12") (pinfunction "2_12") (pintype "unspecified"))
      (node (ref "H3") (pin "19") (pinfunction "19_19") (pintype "unspecified"))
      (node (ref "RN5") (pin "2") (pinfunction "2_2") (pintype "input"))
    )
    (net (code "37") (name "BTN-20") (class "Default")
      (node (ref "ENCODER-17-24") (pin "13") (pinfunction "3_13") (pintype "unspecified"))
      (node (ref "H3") (pin "20") (pinfunction "20_20") (pintype "unspecified"))
      (node (ref "RN5") (pin "1") (pinfunction "1_1") (pintype "input"))
    )
    (net (code "38") (name "BTN-21") (class "Default")
      (node (ref "ENCODER-17-24") (pin "1") (pinfunction "4_1") (pintype "unspecified"))
      (node (ref "H3") (pin "21") (pinfunction "21_21") (pintype "unspecified"))
      (node (ref "RN6") (pin "4") (pinfunction "4_4") (pintype "input"))
    )
    (net (code "39") (name "BTN-22") (class "Default")
      (node (ref "ENCODER-17-24") (pin "2") (pinfunction "5_2") (pintype "unspecified"))
      (node (ref "H3") (pin "22") (pinfunction "22_22") (pintype "unspecified"))
      (node (ref "RN6") (pin "3") (pinfunction "3_3") (pintype "input"))
    )
    (net (code "40") (name "BTN-23") (class "Default")
      (node (ref "ENCODER-17-24") (pin "3") (pinfunction "6_3") (pintype "unspecified"))
      (node (ref "H3") (pin "23") (pinfunction "23_23") (pintype "unspecified"))
      (node (ref "RN6") (pin "2") (pinfunction "2_2") (pintype "input"))
    )
    (net (code "41") (name "BTN-24") (class "Default")
      (node (ref "ENCODER-17-24") (pin "4") (pinfunction "7_4") (pintype "unspecified"))
      (node (ref "H3") (pin "24") (pinfunction "24_24") (pintype "unspecified"))
      (node (ref "RN6") (pin "1") (pinfunction "1_1") (pintype "input"))
    )
    (net (code "42") (name "BTN-25") (class "Default")
      (node (ref "ENCODER-25-32") (pin "10") (pinfunction "0_10") (pintype "unspecified"))
      (node (ref "H3") (pin "25") (pinfunction "25_25") (pintype "unspecified"))
      (node (ref "RN7") (pin "4") (pinfunction "4_4") (pintype "input"))
    )
    (net (code "43") (name "BTN-26") (class "Default")
      (node (ref "ENCODER-25-32") (pin "11") (pinfunction "1_11") (pintype "unspecified"))
      (node (ref "H3") (pin "26") (pinfunction "26_26") (pintype "unspecified"))
      (node (ref "RN7") (pin "3") (pinfunction "3_3") (pintype "input"))
    )
    (net (code "44") (name "BTN-27") (class "Default")
      (node (ref "ENCODER-25-32") (pin "12") (pinfunction "2_12") (pintype "unspecified"))
      (node (ref "H3") (pin "27") (pinfunction "27_27") (pintype "unspecified"))
      (node (ref "RN7") (pin "2") (pinfunction "2_2") (pintype "input"))
    )
    (net (code "45") (name "BTN-28") (class "Default")
      (node (ref "ENCODER-25-32") (pin "13") (pinfunction "3_13") (pintype "unspecified"))
      (node (ref "H3") (pin "28") (pinfunction "28_28") (pintype "unspecified"))
      (node (ref "RN7") (pin "1") (pinfunction "1_1") (pintype "input"))
    )
    (net (code "46") (name "BTN-29") (class "Default")
      (node (ref "ENCODER-25-32") (pin "1") (pinfunction "4_1") (pintype "unspecified"))
      (node (ref "H3") (pin "29") (pinfunction "29_29") (pintype "unspecified"))
      (node (ref "RN8") (pin "4") (pinfunction "4_4") (pintype "input"))
    )
    (net (code "47") (name "BTN-30") (class "Default")
      (node (ref "ENCODER-25-32") (pin "2") (pinfunction "5_2") (pintype "unspecified"))
      (node (ref "H3") (pin "30") (pinfunction "30_30") (pintype "unspecified"))
      (node (ref "RN8") (pin "3") (pinfunction "3_3") (pintype "input"))
    )
    (net (code "48") (name "BTN-31") (class "Default")
      (node (ref "ENCODER-25-32") (pin "3") (pinfunction "6_3") (pintype "unspecified"))
      (node (ref "H3") (pin "31") (pinfunction "31_31") (pintype "unspecified"))
      (node (ref "RN8") (pin "2") (pinfunction "2_2") (pintype "input"))
    )
    (net (code "49") (name "BTN-32") (class "Default")
      (node (ref "ENCODER-25-32") (pin "4") (pinfunction "7_4") (pintype "unspecified"))
      (node (ref "H3") (pin "32") (pinfunction "32_32") (pintype "unspecified"))
      (node (ref "RN8") (pin "1") (pinfunction "1_1") (pintype "input"))
    )
    (net (code "50") (name "BTN-STOP") (class "Default")
      (node (ref "COMPUTER") (pin "5") (pinfunction "5_5") (pintype "unspecified"))
      (node (ref "RN9") (pin "1") (pinfunction "1_1") (pintype "input"))
      (node (ref "STOP-BUTTON") (pin "2") (pinfunction "2_2") (pintype "unspecified"))
    )
    (net (code "51") (name "COIN") (class "Default")
      (node (ref "COINS") (pin "2") (pinfunction "2_2") (pintype "unspecified"))
      (node (ref "COMPUTER") (pin "4") (pinfunction "4_4") (pintype "unspecified"))
      (node (ref "RN9") (pin "3") (pinfunction "3_3") (pintype "input"))
    )
    (net (code "52") (name "DEC-EN-00") (class "Default")
      (node (ref "DECODER-01-08") (pin "4") (pinfunction "E1#_4") (pintype "unspecified"))
      (node (ref "U7") (pin "15") (pinfunction "Y0#_15") (pintype "unspecified"))
    )
    (net (code "53") (name "DEC-EN-01") (class "Default")
      (node (ref "DECODER-09-16") (pin "4") (pinfunction "E1#_4") (pintype "unspecified"))
      (node (ref "U7") (pin "14") (pinfunction "Y1#_14") (pintype "unspecified"))
    )
    (net (code "54") (name "DEC-EN-02") (class "Default")
      (node (ref "DECODER-17-24") (pin "4") (pinfunction "E1#_4") (pintype "unspecified"))
      (node (ref "U7") (pin "13") (pinfunction "Y2#_13") (pintype "unspecified"))
    )
    (net (code "55") (name "DEC-EN-03") (class "Default")
      (node (ref "DECODER-25-32") (pin "4") (pinfunction "E1#_4") (pintype "unspecified"))
      (node (ref "U7") (pin "12") (pinfunction "Y3#_12") (pintype "unspecified"))
    )
    (net (code "56") (name "ENABLE-OUT") (class "Default")
      (node (ref "COMPUTER") (pin "14") (pinfunction "14_14") (pintype "unspecified"))
      (node (ref "DECODER-01-08") (pin "6") (pinfunction "E3_6") (pintype "unspecified"))
      (node (ref "DECODER-09-16") (pin "6") (pinfunction "E3_6") (pintype "unspecified"))
      (node (ref "DECODER-17-24") (pin "6") (pinfunction "E3_6") (pintype "unspecified"))
      (node (ref "DECODER-25-32") (pin "6") (pinfunction "E3_6") (pintype "unspecified"))
      (node (ref "U7") (pin "6") (pinfunction "E3_6") (pintype "unspecified"))
    )
    (net (code "57") (name "ENC-BRG-2-1") (class "Default")
      (node (ref "ENCODER-01-08") (pin "5") (pinfunction "EI_5") (pintype "unspecified"))
      (node (ref "ENCODER-09-16") (pin "15") (pinfunction "EO_15") (pintype "unspecified"))
    )
    (net (code "58") (name "ENC-BRG-3-2") (class "Default")
      (node (ref "ENCODER-09-16") (pin "5") (pinfunction "EI_5") (pintype "unspecified"))
      (node (ref "ENCODER-17-24") (pin "15") (pinfunction "EO_15") (pintype "unspecified"))
    )
    (net (code "59") (name "ENC-BRG-4-3") (class "Default")
      (node (ref "ENCODER-17-24") (pin "5") (pinfunction "EI_5") (pintype "unspecified"))
      (node (ref "ENCODER-25-32") (pin "15") (pinfunction "EO_15") (pintype "unspecified"))
    )
    (net (code "60") (name "ENC-GS-01") (class "Default")
      (node (ref "ENCODER-01-08") (pin "14") (pinfunction "GS_14") (pintype "unspecified"))
      (node (ref "U10") (pin "10") (pinfunction "0_10") (pintype "unspecified"))
    )
    (net (code "61") (name "ENC-GS-02") (class "Default")
      (node (ref "ENCODER-09-16") (pin "14") (pinfunction "GS_14") (pintype "unspecified"))
      (node (ref "U10") (pin "11") (pinfunction "1_11") (pintype "unspecified"))
    )
    (net (code "62") (name "ENC-GS-03") (class "Default")
      (node (ref "ENCODER-17-24") (pin "14") (pinfunction "GS_14") (pintype "unspecified"))
      (node (ref "U10") (pin "12") (pinfunction "2_12") (pintype "unspecified"))
    )
    (net (code "63") (name "ENC-GS-04") (class "Default")
      (node (ref "ENCODER-25-32") (pin "14") (pinfunction "GS_14") (pintype "unspecified"))
      (node (ref "U10") (pin "13") (pinfunction "3_13") (pintype "unspecified"))
    )
    (net (code "64") (name "GND") (class "Default")
      (node (ref "12V") (pin "2") (pinfunction "2_2") (pintype "unspecified"))
      (node (ref "12V-INDICATOR") (pin "1") (pinfunction "-_1") (pintype "unspecified"))
      (node (ref "5V") (pin "2") (pinfunction "2_2") (pintype "unspecified"))
      (node (ref "5V-INDICATOR") (pin "1") (pinfunction "-_1") (pintype "unspecified"))
      (node (ref "CAP-1-ANALOG-REF") (pin "2") (pinfunction "2_2") (pintype "unspecified"))
      (node (ref "CAP-2-ANALOG-REF") (pin "2") (pinfunction "2_2") (pintype "unspecified"))
      (node (ref "CAP-4-ANALOG-REF") (pin "2") (pinfunction "2_2") (pintype "unspecified"))
      (node (ref "COINS") (pin "3") (pinfunction "3_3") (pintype "unspecified"))
      (node (ref "COMPUTER") (pin "22") (pinfunction "22_22") (pintype "unspecified"))
      (node (ref "COMPUTER") (pin "8") (pinfunction "8_8") (pintype "unspecified"))
      (node (ref "CRYSTAL-CAP-1") (pin "1") (pinfunction "1_1") (pintype "input"))
      (node (ref "CRYSTAL-CAP-2") (pin "1") (pinfunction "1_1") (pintype "input"))
      (node (ref "DECODER-01-08") (pin "5") (pinfunction "E2#_5") (pintype "unspecified"))
      (node (ref "DECODER-01-08") (pin "8") (pinfunction "GND_8") (pintype "unspecified"))
      (node (ref "DECODER-09-16") (pin "5") (pinfunction "E2#_5") (pintype "unspecified"))
      (node (ref "DECODER-09-16") (pin "8") (pinfunction "GND_8") (pintype "unspecified"))
      (node (ref "DECODER-17-24") (pin "5") (pinfunction "E2#_5") (pintype "unspecified"))
      (node (ref "DECODER-17-24") (pin "8") (pinfunction "GND_8") (pintype "unspecified"))
      (node (ref "DECODER-25-32") (pin "5") (pinfunction "E2#_5") (pintype "unspecified"))
      (node (ref "DECODER-25-32") (pin "8") (pinfunction "GND_8") (pintype "unspecified"))
      (node (ref "DISPLAY") (pin "1") (pinfunction "1_1") (pintype "unspecified"))
      (node (ref "ENCODER-01-08") (pin "8") (pinfunction "GND_8") (pintype "unspecified"))
      (node (ref "ENCODER-09-16") (pin "8") (pinfunction "GND_8") (pintype "unspecified"))
      (node (ref "ENCODER-17-24") (pin "8") (pinfunction "GND_8") (pintype "unspecified"))
      (node (ref "ENCODER-25-32") (pin "5") (pinfunction "EI_5") (pintype "unspecified"))
      (node (ref "ENCODER-25-32") (pin "8") (pinfunction "GND_8") (pintype "unspecified"))
      (node (ref "H1") (pin "19") (pinfunction "19_19") (pintype "unspecified"))
      (node (ref "H1") (pin "20") (pinfunction "20_20") (pintype "unspecified"))
      (node (ref "H2") (pin "19") (pinfunction "19_19") (pintype "unspecified"))
      (node (ref "H2") (pin "20") (pinfunction "20_20") (pintype "unspecified"))
      (node (ref "ICSP-PROGRAM") (pin "6") (pinfunction "6_6") (pintype "input"))
      (node (ref "PROG-BUTTON") (pin "3") (pinfunction "3_3") (pintype "unspecified"))
      (node (ref "PROG-BUTTON") (pin "4") (pinfunction "4_4") (pintype "unspecified"))
      (node (ref "STOP-BUTTON") (pin "3") (pinfunction "3_3") (pintype "unspecified"))
      (node (ref "U10") (pin "5") (pinfunction "EI_5") (pintype "unspecified"))
      (node (ref "U10") (pin "8") (pinfunction "GND_8") (pintype "unspecified"))
      (node (ref "U2") (pin "7") (pinfunction "VSS_7") (pintype "unspecified"))
      (node (ref "U4") (pin "7") (pinfunction "VSS_7") (pintype "unspecified"))
      (node (ref "U7") (pin "3") (pinfunction "A2_3") (pintype "unspecified"))
      (node (ref "U7") (pin "4") (pinfunction "E1#_4") (pintype "unspecified"))
      (node (ref "U7") (pin "5") (pinfunction "E2#_5") (pintype "unspecified"))
      (node (ref "U7") (pin "8") (pinfunction "GND_8") (pintype "unspecified"))
      (node (ref "X2") (pin "2") (pinfunction "GND_2") (pintype "unspecified"))
      (node (ref "X2") (pin "4") (pinfunction "GND_4") (pintype "unspecified"))
    )
    (net (code "65") (name "ICSP-MISO") (class "Default")
      (node (ref "COMPUTER") (pin "18") (pinfunction "18_18") (pintype "unspecified"))
      (node (ref "ICSP-PROGRAM") (pin "1") (pinfunction "1_1") (pintype "input"))
    )
    (net (code "66") (name "ICSP-MOSI") (class "Default")
      (node (ref "COMPUTER") (pin "17") (pinfunction "17_17") (pintype "unspecified"))
      (node (ref "ICSP-PROGRAM") (pin "4") (pinfunction "4_4") (pintype "input"))
      (node (ref "PROG-BUTTON") (pin "1") (pinfunction "1_1") (pintype "unspecified"))
      (node (ref "PROG-BUTTON") (pin "2") (pinfunction "2_2") (pintype "unspecified"))
      (node (ref "RN9") (pin "2") (pinfunction "2_2") (pintype "input"))
    )
    (net (code "67") (name "ICSP-RESET") (class "Default")
      (node (ref "COMPUTER") (pin "1") (pinfunction "1_1") (pintype "unspecified"))
      (node (ref "ICSP-PROGRAM") (pin "5") (pinfunction "5_5") (pintype "input"))
      (node (ref "RN9") (pin "4") (pinfunction "4_4") (pintype "input"))
    )
    (net (code "68") (name "ICSP-SCK") (class "Default")
      (node (ref "COMPUTER") (pin "19") (pinfunction "19_19") (pintype "unspecified"))
      (node (ref "ICSP-PROGRAM") (pin "3") (pinfunction "3_3") (pintype "input"))
    )
    (net (code "69") (name "INP-00") (class "Default")
      (node (ref "COMPUTER") (pin "15") (pinfunction "15_15") (pintype "unspecified"))
      (node (ref "U4") (pin "1") (pinfunction "J=A*B*C*D_1") (pintype "unspecified"))
    )
    (net (code "70") (name "INP-01") (class "Default")
      (node (ref "COMPUTER") (pin "16") (pinfunction "16_16") (pintype "unspecified"))
      (node (ref "U4") (pin "13") (pinfunction "K=E*F*G*H_13") (pintype "unspecified"))
    )
    (net (code "71") (name "INP-02") (class "Default")
      (node (ref "COMPUTER") (pin "23") (pinfunction "23_23") (pintype "unspecified"))
      (node (ref "COMPUTER") (pin "6") (pinfunction "6_6") (pintype "unspecified"))
      (node (ref "U2") (pin "1") (pinfunction "J=A*B*C*D_1") (pintype "unspecified"))
    )
    (net (code "72") (name "INP-03") (class "Default")
      (node (ref "COMPUTER") (pin "24") (pinfunction "24_24") (pintype "unspecified"))
      (node (ref "U10") (pin "9") (pinfunction "A0_9") (pintype "unspecified"))
    )
    (net (code "73") (name "INP-04") (class "Default")
      (node (ref "COMPUTER") (pin "25") (pinfunction "25_25") (pintype "unspecified"))
      (node (ref "U10") (pin "7") (pinfunction "A1_7") (pintype "unspecified"))
    )
    (net (code "74") (name "INP-ACTIVITY") (class "Default")
      (node (ref "COMPUTER") (pin "26") (pinfunction "26_26") (pintype "unspecified"))
      (node (ref "U10") (pin "14") (pinfunction "GS_14") (pintype "unspecified"))
    )
    (net (code "75") (name "Net-(5V-INDICATOR-+)") (class "Default")
      (node (ref "5V-INDICATOR") (pin "2") (pinfunction "+_2") (pintype "unspecified"))
      (node (ref "R-4-5V-INDICATOR") (pin "2") (pinfunction "2_2") (pintype "input"))
    )
    (net (code "76") (name "Net-(12V-INDICATOR-+)") (class "Default")
      (node (ref "12V-INDICATOR") (pin "2") (pinfunction "+_2") (pintype "unspecified"))
      (node (ref "R-4-12V-INDICATOR") (pin "2") (pinfunction "2_2") (pintype "input"))
    )
    (net (code "77") (name "OUT-00") (class "Default")
      (node (ref "COMPUTER") (pin "2") (pinfunction "2_2") (pintype "unspecified"))
      (node (ref "DECODER-01-08") (pin "1") (pinfunction "A0_1") (pintype "unspecified"))
      (node (ref "DECODER-09-16") (pin "1") (pinfunction "A0_1") (pintype "unspecified"))
      (node (ref "DECODER-17-24") (pin "1") (pinfunction "A0_1") (pintype "unspecified"))
      (node (ref "DECODER-25-32") (pin "1") (pinfunction "A0_1") (pintype "unspecified"))
    )
    (net (code "78") (name "OUT-01") (class "Default")
      (node (ref "COMPUTER") (pin "3") (pinfunction "3_3") (pintype "unspecified"))
      (node (ref "DECODER-01-08") (pin "2") (pinfunction "A1_2") (pintype "unspecified"))
      (node (ref "DECODER-09-16") (pin "2") (pinfunction "A1_2") (pintype "unspecified"))
      (node (ref "DECODER-17-24") (pin "2") (pinfunction "A1_2") (pintype "unspecified"))
      (node (ref "DECODER-25-32") (pin "2") (pinfunction "A1_2") (pintype "unspecified"))
    )
    (net (code "79") (name "OUT-02") (class "Default")
      (node (ref "COMPUTER") (pin "11") (pinfunction "11_11") (pintype "unspecified"))
      (node (ref "DECODER-01-08") (pin "3") (pinfunction "A2_3") (pintype "unspecified"))
      (node (ref "DECODER-09-16") (pin "3") (pinfunction "A2_3") (pintype "unspecified"))
      (node (ref "DECODER-17-24") (pin "3") (pinfunction "A2_3") (pintype "unspecified"))
      (node (ref "DECODER-25-32") (pin "3") (pinfunction "A2_3") (pintype "unspecified"))
    )
    (net (code "80") (name "OUT-03") (class "Default")
      (node (ref "COMPUTER") (pin "12") (pinfunction "12_12") (pintype "unspecified"))
      (node (ref "U7") (pin "1") (pinfunction "A0_1") (pintype "unspecified"))
    )
    (net (code "81") (name "OUT-04") (class "Default")
      (node (ref "COMPUTER") (pin "13") (pinfunction "13_13") (pintype "unspecified"))
      (node (ref "U7") (pin "2") (pinfunction "A1_2") (pintype "unspecified"))
    )
    (net (code "82") (name "RELAY-01") (class "Default")
      (node (ref "DECODER-01-08") (pin "15") (pinfunction "Y0#_15") (pintype "unspecified"))
      (node (ref "H1") (pin "3") (pinfunction "3_3") (pintype "unspecified"))
    )
    (net (code "83") (name "RELAY-02") (class "Default")
      (node (ref "DECODER-01-08") (pin "14") (pinfunction "Y1#_14") (pintype "unspecified"))
      (node (ref "H1") (pin "4") (pinfunction "4_4") (pintype "unspecified"))
    )
    (net (code "84") (name "RELAY-03") (class "Default")
      (node (ref "DECODER-01-08") (pin "13") (pinfunction "Y2#_13") (pintype "unspecified"))
      (node (ref "H1") (pin "5") (pinfunction "5_5") (pintype "unspecified"))
    )
    (net (code "85") (name "RELAY-04") (class "Default")
      (node (ref "DECODER-01-08") (pin "12") (pinfunction "Y3#_12") (pintype "unspecified"))
      (node (ref "H1") (pin "6") (pinfunction "6_6") (pintype "unspecified"))
    )
    (net (code "86") (name "RELAY-05") (class "Default")
      (node (ref "DECODER-01-08") (pin "11") (pinfunction "Y4#_11") (pintype "unspecified"))
      (node (ref "H1") (pin "7") (pinfunction "7_7") (pintype "unspecified"))
    )
    (net (code "87") (name "RELAY-06") (class "Default")
      (node (ref "DECODER-01-08") (pin "10") (pinfunction "Y5#_10") (pintype "unspecified"))
      (node (ref "H1") (pin "8") (pinfunction "8_8") (pintype "unspecified"))
    )
    (net (code "88") (name "RELAY-07") (class "Default")
      (node (ref "DECODER-01-08") (pin "9") (pinfunction "Y6#_9") (pintype "unspecified"))
      (node (ref "H1") (pin "9") (pinfunction "9_9") (pintype "unspecified"))
    )
    (net (code "89") (name "RELAY-08") (class "Default")
      (node (ref "DECODER-01-08") (pin "7") (pinfunction "Y7#_7") (pintype "unspecified"))
      (node (ref "H1") (pin "10") (pinfunction "10_10") (pintype "unspecified"))
    )
    (net (code "90") (name "RELAY-09") (class "Default")
      (node (ref "DECODER-09-16") (pin "15") (pinfunction "Y0#_15") (pintype "unspecified"))
      (node (ref "H1") (pin "11") (pinfunction "11_11") (pintype "unspecified"))
    )
    (net (code "91") (name "RELAY-10") (class "Default")
      (node (ref "DECODER-09-16") (pin "14") (pinfunction "Y1#_14") (pintype "unspecified"))
      (node (ref "H1") (pin "12") (pinfunction "12_12") (pintype "unspecified"))
    )
    (net (code "92") (name "RELAY-11") (class "Default")
      (node (ref "DECODER-09-16") (pin "13") (pinfunction "Y2#_13") (pintype "unspecified"))
      (node (ref "H1") (pin "13") (pinfunction "13_13") (pintype "unspecified"))
    )
    (net (code "93") (name "RELAY-12") (class "Default")
      (node (ref "DECODER-09-16") (pin "12") (pinfunction "Y3#_12") (pintype "unspecified"))
      (node (ref "H1") (pin "14") (pinfunction "14_14") (pintype "unspecified"))
    )
    (net (code "94") (name "RELAY-13") (class "Default")
      (node (ref "DECODER-09-16") (pin "11") (pinfunction "Y4#_11") (pintype "unspecified"))
      (node (ref "H1") (pin "15") (pinfunction "15_15") (pintype "unspecified"))
    )
    (net (code "95") (name "RELAY-14") (class "Default")
      (node (ref "DECODER-09-16") (pin "10") (pinfunction "Y5#_10") (pintype "unspecified"))
      (node (ref "H1") (pin "16") (pinfunction "16_16") (pintype "unspecified"))
    )
    (net (code "96") (name "RELAY-15") (class "Default")
      (node (ref "DECODER-09-16") (pin "9") (pinfunction "Y6#_9") (pintype "unspecified"))
      (node (ref "H1") (pin "17") (pinfunction "17_17") (pintype "unspecified"))
    )
    (net (code "97") (name "RELAY-16") (class "Default")
      (node (ref "DECODER-09-16") (pin "7") (pinfunction "Y7#_7") (pintype "unspecified"))
      (node (ref "H1") (pin "18") (pinfunction "18_18") (pintype "unspecified"))
    )
    (net (code "98") (name "RELAY-17") (class "Default")
      (node (ref "DECODER-17-24") (pin "15") (pinfunction "Y0#_15") (pintype "unspecified"))
      (node (ref "H2") (pin "3") (pinfunction "3_3") (pintype "unspecified"))
    )
    (net (code "99") (name "RELAY-18") (class "Default")
      (node (ref "DECODER-17-24") (pin "14") (pinfunction "Y1#_14") (pintype "unspecified"))
      (node (ref "H2") (pin "4") (pinfunction "4_4") (pintype "unspecified"))
    )
    (net (code "100") (name "RELAY-19") (class "Default")
      (node (ref "DECODER-17-24") (pin "13") (pinfunction "Y2#_13") (pintype "unspecified"))
      (node (ref "H2") (pin "5") (pinfunction "5_5") (pintype "unspecified"))
    )
    (net (code "101") (name "RELAY-20") (class "Default")
      (node (ref "DECODER-17-24") (pin "12") (pinfunction "Y3#_12") (pintype "unspecified"))
      (node (ref "H2") (pin "6") (pinfunction "6_6") (pintype "unspecified"))
    )
    (net (code "102") (name "RELAY-21") (class "Default")
      (node (ref "DECODER-17-24") (pin "11") (pinfunction "Y4#_11") (pintype "unspecified"))
      (node (ref "H2") (pin "7") (pinfunction "7_7") (pintype "unspecified"))
    )
    (net (code "103") (name "RELAY-22") (class "Default")
      (node (ref "DECODER-17-24") (pin "10") (pinfunction "Y5#_10") (pintype "unspecified"))
      (node (ref "H2") (pin "8") (pinfunction "8_8") (pintype "unspecified"))
    )
    (net (code "104") (name "RELAY-23") (class "Default")
      (node (ref "DECODER-17-24") (pin "9") (pinfunction "Y6#_9") (pintype "unspecified"))
      (node (ref "H2") (pin "9") (pinfunction "9_9") (pintype "unspecified"))
    )
    (net (code "105") (name "RELAY-24") (class "Default")
      (node (ref "DECODER-17-24") (pin "7") (pinfunction "Y7#_7") (pintype "unspecified"))
      (node (ref "H2") (pin "10") (pinfunction "10_10") (pintype "unspecified"))
    )
    (net (code "106") (name "RELAY-25") (class "Default")
      (node (ref "DECODER-25-32") (pin "15") (pinfunction "Y0#_15") (pintype "unspecified"))
      (node (ref "H2") (pin "11") (pinfunction "11_11") (pintype "unspecified"))
    )
    (net (code "107") (name "RELAY-26") (class "Default")
      (node (ref "DECODER-25-32") (pin "14") (pinfunction "Y1#_14") (pintype "unspecified"))
      (node (ref "H2") (pin "12") (pinfunction "12_12") (pintype "unspecified"))
    )
    (net (code "108") (name "RELAY-27") (class "Default")
      (node (ref "DECODER-25-32") (pin "13") (pinfunction "Y2#_13") (pintype "unspecified"))
      (node (ref "H2") (pin "13") (pinfunction "13_13") (pintype "unspecified"))
    )
    (net (code "109") (name "RELAY-28") (class "Default")
      (node (ref "DECODER-25-32") (pin "12") (pinfunction "Y3#_12") (pintype "unspecified"))
      (node (ref "H2") (pin "14") (pinfunction "14_14") (pintype "unspecified"))
    )
    (net (code "110") (name "RELAY-29") (class "Default")
      (node (ref "DECODER-25-32") (pin "11") (pinfunction "Y4#_11") (pintype "unspecified"))
      (node (ref "H2") (pin "15") (pinfunction "15_15") (pintype "unspecified"))
    )
    (net (code "111") (name "RELAY-30") (class "Default")
      (node (ref "DECODER-25-32") (pin "10") (pinfunction "Y5#_10") (pintype "unspecified"))
      (node (ref "H2") (pin "16") (pinfunction "16_16") (pintype "unspecified"))
    )
    (net (code "112") (name "RELAY-31") (class "Default")
      (node (ref "DECODER-25-32") (pin "9") (pinfunction "Y6#_9") (pintype "unspecified"))
      (node (ref "H2") (pin "17") (pinfunction "17_17") (pintype "unspecified"))
    )
    (net (code "113") (name "RELAY-32") (class "Default")
      (node (ref "DECODER-25-32") (pin "7") (pinfunction "Y7#_7") (pintype "unspecified"))
      (node (ref "H2") (pin "18") (pinfunction "18_18") (pintype "unspecified"))
    )
    (net (code "114") (name "SCL") (class "Default")
      (node (ref "COMPUTER") (pin "28") (pinfunction "28_28") (pintype "unspecified"))
      (node (ref "DISPLAY") (pin "4") (pinfunction "4_4") (pintype "unspecified"))
    )
    (net (code "115") (name "SDA") (class "Default")
      (node (ref "COMPUTER") (pin "27") (pinfunction "27_27") (pintype "unspecified"))
      (node (ref "DISPLAY") (pin "3") (pinfunction "3_3") (pintype "unspecified"))
    )
    (net (code "116") (name "unconnected-(ENCODER-01-08-EO-Pad15)") (class "Default")
      (node (ref "ENCODER-01-08") (pin "15") (pinfunction "EO_15") (pintype "unspecified+no_connect"))
    )
    (net (code "117") (name "unconnected-(U2-E-Pad9)") (class "Default")
      (node (ref "U2") (pin "9") (pinfunction "E_9") (pintype "unspecified+no_connect"))
    )
    (net (code "118") (name "unconnected-(U2-F-Pad10)") (class "Default")
      (node (ref "U2") (pin "10") (pinfunction "F_10") (pintype "unspecified+no_connect"))
    )
    (net (code "119") (name "unconnected-(U2-G-Pad11)") (class "Default")
      (node (ref "U2") (pin "11") (pinfunction "G_11") (pintype "unspecified+no_connect"))
    )
    (net (code "120") (name "unconnected-(U2-H-Pad12)") (class "Default")
      (node (ref "U2") (pin "12") (pinfunction "H_12") (pintype "unspecified+no_connect"))
    )
    (net (code "121") (name "unconnected-(U2-K=E*F*G*H-Pad13)") (class "Default")
      (node (ref "U2") (pin "13") (pinfunction "K=E*F*G*H_13") (pintype "unspecified+no_connect"))
    )
    (net (code "122") (name "unconnected-(U2-NC-Pad6)") (class "Default")
      (node (ref "U2") (pin "6") (pinfunction "NC_6") (pintype "unspecified+no_connect"))
    )
    (net (code "123") (name "unconnected-(U2-NC-Pad8)") (class "Default")
      (node (ref "U2") (pin "8") (pinfunction "NC_8") (pintype "unspecified+no_connect"))
    )
    (net (code "124") (name "unconnected-(U4-NC-Pad6)") (class "Default")
      (node (ref "U4") (pin "6") (pinfunction "NC_6") (pintype "unspecified+no_connect"))
    )
    (net (code "125") (name "unconnected-(U4-NC-Pad8)") (class "Default")
      (node (ref "U4") (pin "8") (pinfunction "NC_8") (pintype "unspecified+no_connect"))
    )
    (net (code "126") (name "unconnected-(U7-Y4#-Pad11)") (class "Default")
      (node (ref "U7") (pin "11") (pinfunction "Y4#_11") (pintype "unspecified+no_connect"))
    )
    (net (code "127") (name "unconnected-(U7-Y5#-Pad10)") (class "Default")
      (node (ref "U7") (pin "10") (pinfunction "Y5#_10") (pintype "unspecified+no_connect"))
    )
    (net (code "128") (name "unconnected-(U7-Y6#-Pad9)") (class "Default")
      (node (ref "U7") (pin "9") (pinfunction "Y6#_9") (pintype "unspecified+no_connect"))
    )
    (net (code "129") (name "unconnected-(U7-Y7#-Pad7)") (class "Default")
      (node (ref "U7") (pin "7") (pinfunction "Y7#_7") (pintype "unspecified+no_connect"))
    )
    (net (code "130") (name "unconnected-(U10-A2-Pad6)") (class "Default")
      (node (ref "U10") (pin "6") (pinfunction "A2_6") (pintype "unspecified+no_connect"))
    )
    (net (code "131") (name "unconnected-(U10-EO-Pad15)") (class "Default")
      (node (ref "U10") (pin "15") (pinfunction "EO_15") (pintype "unspecified+no_connect"))
    )
  )
)
